# source_eagle.net
KiCad netlist of a schematic drawn in EAGLE
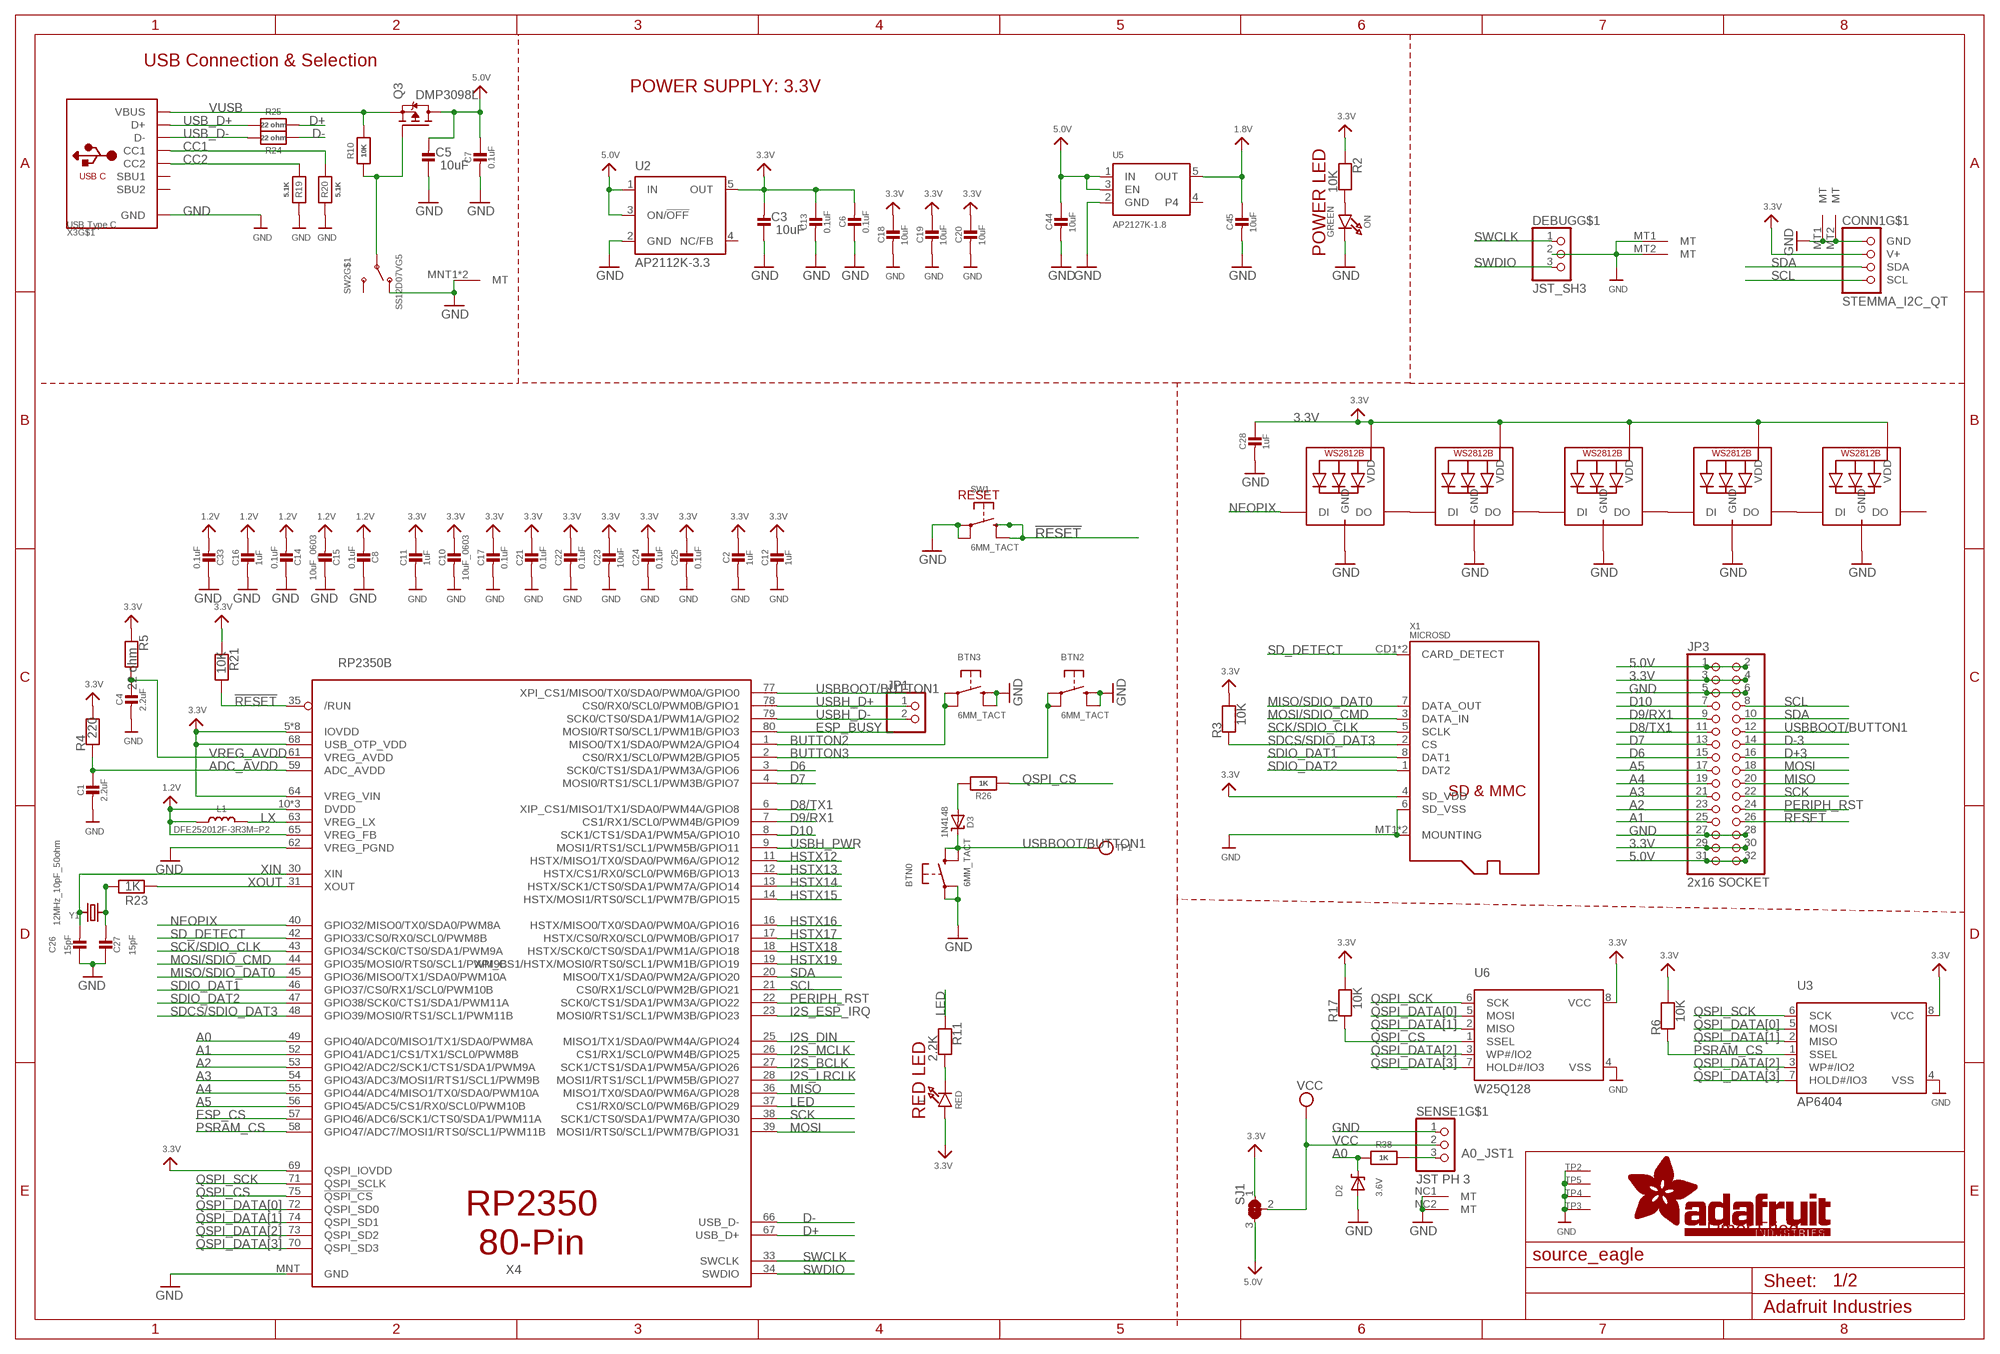
[diagram p0: schematic, sheet 1]
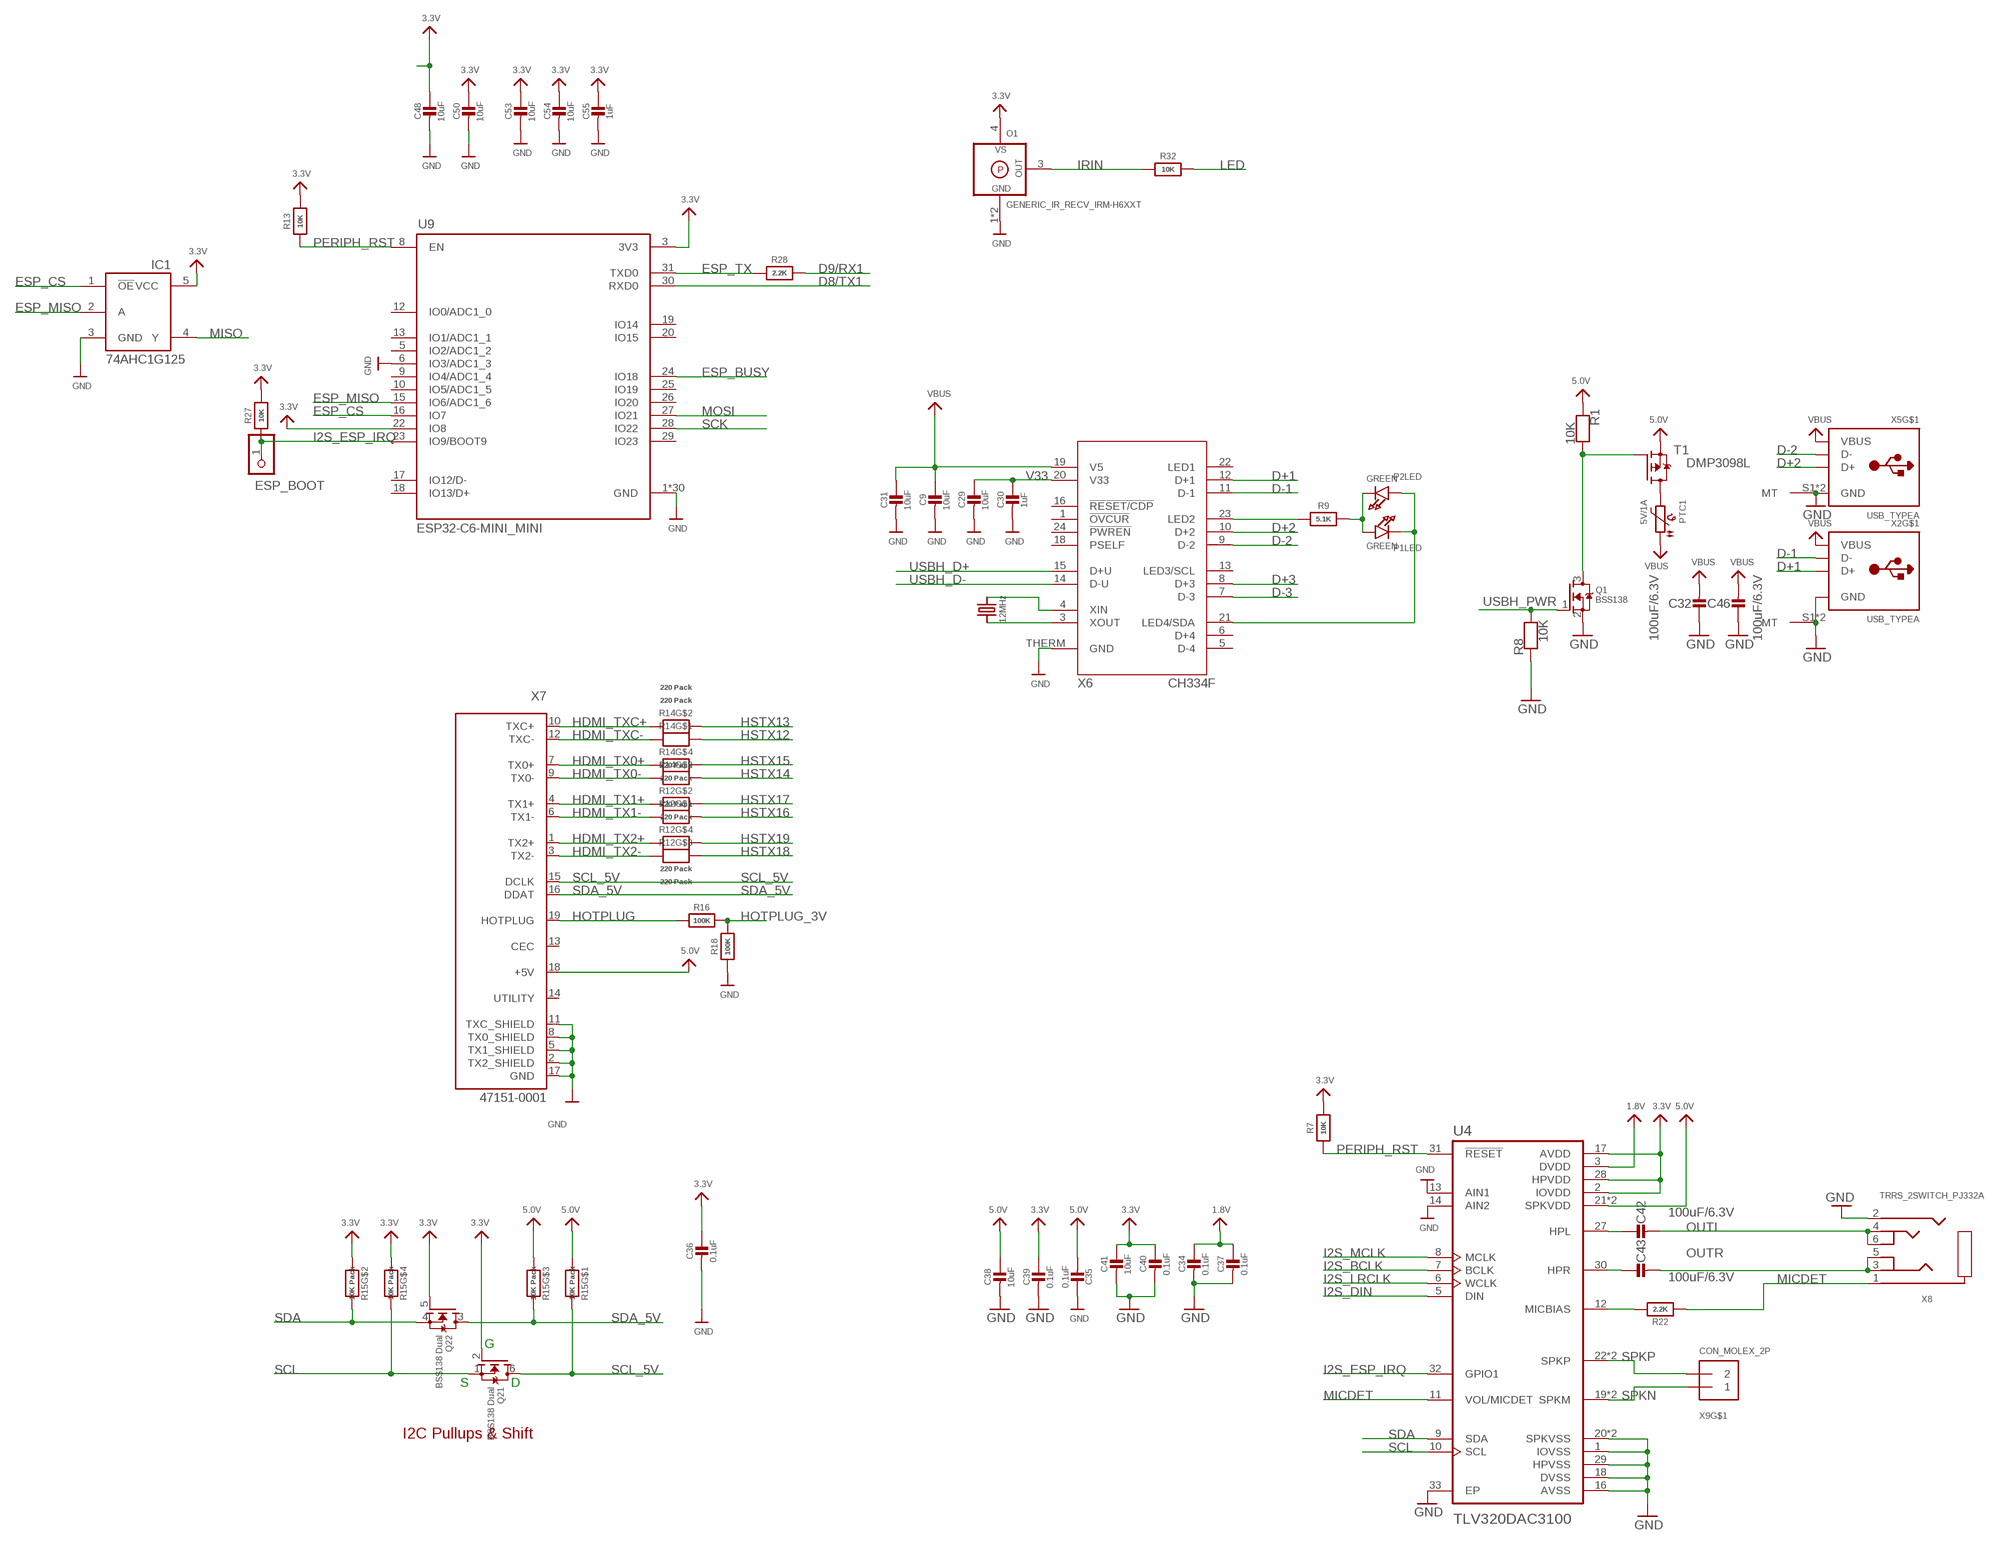
[diagram p1: schematic, sheet 2]

(export (version "E")
  (design (tool "Eeschema 10.0.6"))
  (components
    (comp (ref "BTN0")
      (value "6MM_TACT")
      (footprint "eagle-import:EVQ-Q2")
      (libsource (lib "eagle-import") (part "SWITCH_TACT_SMT"))
    )
    (comp (ref "BTN2")
      (value "6MM_TACT")
      (footprint "eagle-import:EVQ-Q2")
      (libsource (lib "eagle-import") (part "SWITCH_TACT_SMT"))
    )
    (comp (ref "BTN3")
      (value "6MM_TACT")
      (footprint "eagle-import:EVQ-Q2")
      (libsource (lib "eagle-import") (part "SWITCH_TACT_SMT"))
    )
    (comp (ref "C1")
      (value "2.2uF")
      (footprint "eagle-import:0603-NO")
      (libsource (lib "eagle-import") (part "CAP_CERAMIC0603_NO"))
    )
    (comp (ref "C2")
      (value "1uF")
      (footprint "eagle-import:0603-NO")
      (libsource (lib "eagle-import") (part "CAP_CERAMIC0603_NO"))
    )
    (comp (ref "C3")
      (value "10uF")
      (footprint "eagle-import:0805-NO")
      (libsource (lib "eagle-import") (part "CAP_CERAMIC0805-NOOUTLINE"))
    )
    (comp (ref "C4")
      (value "2.2uF")
      (footprint "eagle-import:0603-NO")
      (libsource (lib "eagle-import") (part "CAP_CERAMIC0603_NO"))
    )
    (comp (ref "C5")
      (value "10uF")
      (footprint "eagle-import:0805-NO")
      (libsource (lib "eagle-import") (part "CAP_CERAMIC0805-NOOUTLINE"))
    )
    (comp (ref "C6")
      (value "0.1uF")
      (footprint "eagle-import:0603-NO")
      (libsource (lib "eagle-import") (part "CAP_CERAMIC0603_NO"))
    )
    (comp (ref "C7")
      (value "0.1uF")
      (footprint "eagle-import:0603-NO")
      (libsource (lib "eagle-import") (part "CAP_CERAMIC0603_NO"))
    )
    (comp (ref "C8")
      (value "0.1uF")
      (footprint "eagle-import:0603-NO")
      (libsource (lib "eagle-import") (part "CAP_CERAMIC0603_NO"))
    )
    (comp (ref "C10")
      (value "10uF_0603")
      (footprint "eagle-import:0603-NO_WIDE")
      (libsource (lib "eagle-import") (part "CAP_CERAMIC_0603WIDE"))
    )
    (comp (ref "C11")
      (value "1uF")
      (footprint "eagle-import:0603-NO")
      (libsource (lib "eagle-import") (part "CAP_CERAMIC0603_NO"))
    )
    (comp (ref "C12")
      (value "1uF")
      (footprint "eagle-import:0603-NO")
      (libsource (lib "eagle-import") (part "CAP_CERAMIC0603_NO"))
    )
    (comp (ref "C13")
      (value "0.1uF")
      (footprint "eagle-import:0603-NO")
      (libsource (lib "eagle-import") (part "CAP_CERAMIC0603_NO"))
    )
    (comp (ref "C14")
      (value "0.1uF")
      (footprint "eagle-import:0603-NO")
      (libsource (lib "eagle-import") (part "CAP_CERAMIC0603_NO"))
    )
    (comp (ref "C15")
      (value "10uF_0603")
      (footprint "eagle-import:0603-NO_WIDE")
      (libsource (lib "eagle-import") (part "CAP_CERAMIC_0603WIDE"))
    )
    (comp (ref "C16")
      (value "1uF")
      (footprint "eagle-import:0603-NO")
      (libsource (lib "eagle-import") (part "CAP_CERAMIC0603_NO"))
    )
    (comp (ref "C17")
      (value "0.1uF")
      (footprint "eagle-import:0603-NO")
      (libsource (lib "eagle-import") (part "CAP_CERAMIC0603_NO"))
    )
    (comp (ref "C18")
      (value "10uF")
      (footprint "eagle-import:0805-NO")
      (libsource (lib "eagle-import") (part "CAP_CERAMIC0805-NOOUTLINE"))
    )
    (comp (ref "C19")
      (value "10uF")
      (footprint "eagle-import:0805-NO")
      (libsource (lib "eagle-import") (part "CAP_CERAMIC0805-NOOUTLINE"))
    )
    (comp (ref "C20")
      (value "10uF")
      (footprint "eagle-import:0805-NO")
      (libsource (lib "eagle-import") (part "CAP_CERAMIC0805-NOOUTLINE"))
    )
    (comp (ref "C21")
      (value "0.1uF")
      (footprint "eagle-import:0603-NO")
      (libsource (lib "eagle-import") (part "CAP_CERAMIC0603_NO"))
    )
    (comp (ref "C22")
      (value "0.1uF")
      (footprint "eagle-import:0603-NO")
      (libsource (lib "eagle-import") (part "CAP_CERAMIC0603_NO"))
    )
    (comp (ref "C23")
      (value "10uF")
      (footprint "eagle-import:0805-NO")
      (libsource (lib "eagle-import") (part "CAP_CERAMIC0805-NOOUTLINE"))
    )
    (comp (ref "C24")
      (value "0.1uF")
      (footprint "eagle-import:0603-NO")
      (libsource (lib "eagle-import") (part "CAP_CERAMIC0603_NO"))
    )
    (comp (ref "C25")
      (value "0.1uF")
      (footprint "eagle-import:0603-NO")
      (libsource (lib "eagle-import") (part "CAP_CERAMIC0603_NO"))
    )
    (comp (ref "C26")
      (value "15pF")
      (footprint "eagle-import:0603-NO")
      (libsource (lib "eagle-import") (part "CAP_CERAMIC0603_NO"))
    )
    (comp (ref "C27")
      (value "15pF")
      (footprint "eagle-import:0603-NO")
      (libsource (lib "eagle-import") (part "CAP_CERAMIC0603_NO"))
    )
    (comp (ref "C28")
      (value "1uF")
      (footprint "eagle-import:0603-NO")
      (libsource (lib "eagle-import") (part "CAP_CERAMIC0603_NO"))
    )
    (comp (ref "C33")
      (value "0.1uF")
      (footprint "eagle-import:0603-NO")
      (libsource (lib "eagle-import") (part "CAP_CERAMIC0603_NO"))
    )
    (comp (ref "C44")
      (value "10uF")
      (footprint "eagle-import:0805-NO")
      (libsource (lib "eagle-import") (part "CAP_CERAMIC0805-NOOUTLINE"))
    )
    (comp (ref "C45")
      (value "10uF")
      (footprint "eagle-import:0805-NO")
      (libsource (lib "eagle-import") (part "CAP_CERAMIC0805-NOOUTLINE"))
    )
    (comp (ref "CONN1")
      (value "STEMMA_I2C_QT")
      (footprint "eagle-import:JST_SH4")
      (libsource (lib "eagle-import") (part "STEMMA_I2C_QT"))
    )
    (comp (ref "D2")
      (value "3.6V")
      (footprint "eagle-import:SOD-323")
      (libsource (lib "eagle-import") (part "DIODE-ZENERSOD323"))
    )
    (comp (ref "D3")
      (value "1N4148")
      (footprint "eagle-import:SOD-323")
      (libsource (lib "eagle-import") (part "DIODE-SCHOTTKYSOD-323"))
    )
    (comp (ref "DEBUG")
      (value "JST_SH3")
      (footprint "eagle-import:JST_SH3_RA")
      (libsource (lib "eagle-import") (part "CON_JST_SH_3PINVERT"))
    )
    (comp (ref "JP1")
      (value "HEADER-1X2ROUND")
      (footprint "eagle-import:1X02_ROUND")
      (libsource (lib "eagle-import") (part "HEADER-1X2ROUND"))
    )
    (comp (ref "JP3")
      (value "2x16 SOCKET")
      (footprint "eagle-import:2X16")
      (libsource (lib "eagle-import") (part "PINHD-2X16"))
    )
    (comp (ref "L")
      (value "RED")
      (footprint "eagle-import:CHIPLED_0603_NOOUTLINE")
      (libsource (lib "eagle-import") (part "LED0603_NOOUTLINE"))
    )
    (comp (ref "L1")
      (value "DFE252012F-3R3M=P2")
      (footprint "eagle-import:INDUCTOR_1007")
      (libsource (lib "eagle-import") (part "INDUCTOR"))
    )
    (comp (ref "LED1")
      (value "WS2812B_3535FULL")
      (footprint "eagle-import:LED3535_FULLPADS")
      (libsource (lib "eagle-import") (part "WS2812B_3535FULL"))
    )
    (comp (ref "LED2")
      (value "WS2812B_3535FULL")
      (footprint "eagle-import:LED3535_FULLPADS")
      (libsource (lib "eagle-import") (part "WS2812B_3535FULL"))
    )
    (comp (ref "LED3")
      (value "WS2812B_3535FULL")
      (footprint "eagle-import:LED3535_FULLPADS")
      (libsource (lib "eagle-import") (part "WS2812B_3535FULL"))
    )
    (comp (ref "LED4")
      (value "WS2812B_3535FULL")
      (footprint "eagle-import:LED3535_FULLPADS")
      (libsource (lib "eagle-import") (part "WS2812B_3535FULL"))
    )
    (comp (ref "LED5")
      (value "WS2812B_3535FULL")
      (footprint "eagle-import:LED3535_FULLPADS")
      (libsource (lib "eagle-import") (part "WS2812B_3535FULL"))
    )
    (comp (ref "ON")
      (value "GREEN")
      (footprint "eagle-import:CHIPLED_0603_NOOUTLINE")
      (libsource (lib "eagle-import") (part "LED0603_NOOUTLINE"))
    )
    (comp (ref "Q3")
      (value "DMP3098L")
      (footprint "eagle-import:SOT23-WIDE")
      (libsource (lib "eagle-import") (part "MOSFET-PWIDE"))
    )
    (comp (ref "R2")
      (value "10K")
      (footprint "eagle-import:0603-NO")
      (libsource (lib "eagle-import") (part "RESISTOR_0603_NOOUT"))
    )
    (comp (ref "R3")
      (value "10K")
      (footprint "eagle-import:0603-NO")
      (libsource (lib "eagle-import") (part "RESISTOR_0603_NOOUT"))
    )
    (comp (ref "R4")
      (value "220")
      (footprint "eagle-import:0603-NO")
      (libsource (lib "eagle-import") (part "RESISTOR_0603_NOOUT"))
    )
    (comp (ref "R5")
      (value "22 ohm")
      (footprint "eagle-import:0603-NO")
      (libsource (lib "eagle-import") (part "RESISTOR_0603_NOOUT"))
    )
    (comp (ref "R6")
      (value "10K")
      (footprint "eagle-import:0603-NO")
      (libsource (lib "eagle-import") (part "RESISTOR_0603_NOOUT"))
    )
    (comp (ref "R10")
      (value "10K")
      (footprint "eagle-import:0603-NO")
      (libsource (lib "eagle-import") (part "RESISTOR_0603_NOOUT"))
    )
    (comp (ref "R11")
      (value "2.2K")
      (footprint "eagle-import:0603-NO")
      (libsource (lib "eagle-import") (part "RESISTOR_0603_NOOUT"))
    )
    (comp (ref "R17")
      (value "10K")
      (footprint "eagle-import:0603-NO")
      (libsource (lib "eagle-import") (part "RESISTOR_0603_NOOUT"))
    )
    (comp (ref "R19")
      (value "5.1K")
      (footprint "eagle-import:0603-NO")
      (libsource (lib "eagle-import") (part "RESISTOR_0603_NOOUT"))
    )
    (comp (ref "R20")
      (value "5.1K")
      (footprint "eagle-import:0603-NO")
      (libsource (lib "eagle-import") (part "RESISTOR_0603_NOOUT"))
    )
    (comp (ref "R21")
      (value "10K")
      (footprint "eagle-import:0603-NO")
      (libsource (lib "eagle-import") (part "RESISTOR_0603_NOOUT"))
    )
    (comp (ref "R23")
      (value "1K")
      (footprint "eagle-import:0603-NO")
      (libsource (lib "eagle-import") (part "RESISTOR_0603_NOOUT"))
    )
    (comp (ref "R24")
      (value "22 ohm")
      (footprint "eagle-import:0603-NO")
      (libsource (lib "eagle-import") (part "RESISTOR_0603_NOOUT"))
    )
    (comp (ref "R25")
      (value "22 ohm")
      (footprint "eagle-import:0603-NO")
      (libsource (lib "eagle-import") (part "RESISTOR_0603_NOOUT"))
    )
    (comp (ref "R26")
      (value "1K")
      (footprint "eagle-import:0603-NO")
      (libsource (lib "eagle-import") (part "RESISTOR_0603_NOOUT"))
    )
    (comp (ref "R38")
      (value "1K")
      (footprint "eagle-import:0603-NO")
      (libsource (lib "eagle-import") (part "RESISTOR_0603_NOOUT"))
    )
    (comp (ref "SENSE1")
      (value "JST PH 3")
      (footprint "eagle-import:JSTPH3")
      (libsource (lib "eagle-import") (part "CON_JST_PH_3PIN"))
    )
    (comp (ref "SJ1")
      (value "SOLDERJUMPER_2WAY")
      (footprint "eagle-import:SOLDERJUMPER_2WAY_OPEN_NOPASTE")
      (libsource (lib "eagle-import") (part "SOLDERJUMPER_2WAY"))
    )
    (comp (ref "SW1")
      (value "6MM_TACT")
      (footprint "eagle-import:EVQ-Q2")
      (libsource (lib "eagle-import") (part "SWITCH_TACT_SMT"))
    )
    (comp (ref "SW2")
      (value "SS12D07VG5")
      (footprint "eagle-import:SPDT_SS12D07VG5")
      (libsource (lib "eagle-import") (part "SWITCH_SPDTSS12D07VG5"))
    )
    (comp (ref "TP1")
      (value "TESTPOINTROUND1.5MMNO")
      (footprint "eagle-import:TESTPOINT_ROUND_1.5MM_NO")
      (libsource (lib "eagle-import") (part "TESTPOINTROUND1.5MMNO"))
    )
    (comp (ref "TP2")
      (value "DNP")
      (footprint "eagle-import:SMT_NUT_3MM")
      (libsource (lib "eagle-import") (part "SEWTAP_SMTNUTM3"))
    )
    (comp (ref "TP3")
      (value "SEWTAP_SMTNUTM3")
      (footprint "eagle-import:SMT_NUT_3MM")
      (libsource (lib "eagle-import") (part "SEWTAP_SMTNUTM3"))
    )
    (comp (ref "TP4")
      (value "SEWTAP_SMTNUTM3")
      (footprint "eagle-import:SMT_NUT_3MM")
      (libsource (lib "eagle-import") (part "SEWTAP_SMTNUTM3"))
    )
    (comp (ref "TP5")
      (value "SEWTAP_SMTNUTM3")
      (footprint "eagle-import:SMT_NUT_3MM")
      (libsource (lib "eagle-import") (part "SEWTAP_SMTNUTM3"))
    )
    (comp (ref "U2")
      (value "AP2112K-3.3")
      (footprint "eagle-import:SOT23-DBV")
      (libsource (lib "eagle-import") (part "LP2985-XXDBVR33"))
    )
    (comp (ref "U3")
      (value "AP6404")
      (footprint "eagle-import:SOIC8_208MIL")
      (libsource (lib "eagle-import") (part "SPIFLASH_8PIN208MIL"))
    )
    (comp (ref "U5")
      (value "AP2127K-1.8")
      (footprint "eagle-import:SOT23-5")
      (libsource (lib "eagle-import") (part "VREG_SOT23-5"))
    )
    (comp (ref "U6")
      (value "W25Q128")
      (footprint "eagle-import:SOIC8_208MIL")
      (libsource (lib "eagle-import") (part "SPIFLASH_8PIN208MIL"))
    )
    (comp (ref "X1")
      (value "MICROSD")
      (footprint "eagle-import:MICROSD")
      (libsource (lib "eagle-import") (part "MICROSD"))
    )
    (comp (ref "X3")
      (value "USB Type C")
      (footprint "eagle-import:USB_C_CUSB31-CFM2AX-01-X")
      (libsource (lib "eagle-import") (part "USB_C"))
    )
    (comp (ref "X4")
      (value "RP2350B")
      (footprint "eagle-import:QFN80")
      (libsource (lib "eagle-import") (part "RP2350B"))
    )
    (comp (ref "Y1")
      (value "12MHz_10pF_50ohm")
      (footprint "eagle-import:CRYSTAL_2.5X2")
      (libsource (lib "eagle-import") (part "CRYSTAL2.5X2.0"))
    )
    (comp (ref "C9")
      (value "10uF")
      (footprint "eagle-import:0805-NO")
      (libsource (lib "eagle-import") (part "CAP_CERAMIC0805-NOOUTLINE"))
    )
    (comp (ref "C29")
      (value "10uF")
      (footprint "eagle-import:0805-NO")
      (libsource (lib "eagle-import") (part "CAP_CERAMIC0805-NOOUTLINE"))
    )
    (comp (ref "C30")
      (value "1uF")
      (footprint "eagle-import:0603-NO")
      (libsource (lib "eagle-import") (part "CAP_CERAMIC0603_NO"))
    )
    (comp (ref "C31")
      (value "10uF")
      (footprint "eagle-import:0805-NO")
      (libsource (lib "eagle-import") (part "CAP_CERAMIC0805-NOOUTLINE"))
    )
    (comp (ref "C32")
      (value "100uF/6.3V")
      (footprint "eagle-import:_1206")
      (libsource (lib "eagle-import") (part "CAP_CERAMIC_1206"))
    )
    (comp (ref "C34")
      (value "0.1uF")
      (footprint "eagle-import:0603-NO")
      (libsource (lib "eagle-import") (part "CAP_CERAMIC0603_NO"))
    )
    (comp (ref "C35")
      (value "0.1uF")
      (footprint "eagle-import:0603-NO")
      (libsource (lib "eagle-import") (part "CAP_CERAMIC0603_NO"))
    )
    (comp (ref "C36")
      (value "0.1uF")
      (footprint "eagle-import:0603-NO")
      (libsource (lib "eagle-import") (part "CAP_CERAMIC0603_NO"))
    )
    (comp (ref "C37")
      (value "0.1uF")
      (footprint "eagle-import:0603-NO")
      (libsource (lib "eagle-import") (part "CAP_CERAMIC0603_NO"))
    )
    (comp (ref "C38")
      (value "10uF")
      (footprint "eagle-import:0805-NO")
      (libsource (lib "eagle-import") (part "CAP_CERAMIC0805-NOOUTLINE"))
    )
    (comp (ref "C39")
      (value "0.1uF")
      (footprint "eagle-import:0603-NO")
      (libsource (lib "eagle-import") (part "CAP_CERAMIC0603_NO"))
    )
    (comp (ref "C40")
      (value "0.1uF")
      (footprint "eagle-import:0603-NO")
      (libsource (lib "eagle-import") (part "CAP_CERAMIC0603_NO"))
    )
    (comp (ref "C41")
      (value "10uF")
      (footprint "eagle-import:0805-NO")
      (libsource (lib "eagle-import") (part "CAP_CERAMIC0805-NOOUTLINE"))
    )
    (comp (ref "C42")
      (value "100uF/6.3V")
      (footprint "eagle-import:_1206")
      (libsource (lib "eagle-import") (part "CAP_CERAMIC_1206"))
    )
    (comp (ref "C43")
      (value "100uF/6.3V")
      (footprint "eagle-import:_1206")
      (libsource (lib "eagle-import") (part "CAP_CERAMIC_1206"))
    )
    (comp (ref "C46")
      (value "100uF/6.3V")
      (footprint "eagle-import:_1206")
      (libsource (lib "eagle-import") (part "CAP_CERAMIC_1206"))
    )
    (comp (ref "C48")
      (value "10uF")
      (footprint "eagle-import:0805-NO")
      (fields (field (name "REV") "C"))
      (libsource (lib "eagle-import") (part "CAP_CERAMIC0805-NOOUTLINE"))
    )
    (comp (ref "C50")
      (value "10uF")
      (footprint "eagle-import:0805-NO")
      (libsource (lib "eagle-import") (part "CAP_CERAMIC0805-NOOUTLINE"))
    )
    (comp (ref "C53")
      (value "10uF")
      (footprint "eagle-import:0805-NO")
      (libsource (lib "eagle-import") (part "CAP_CERAMIC0805-NOOUTLINE"))
    )
    (comp (ref "C54")
      (value "10uF")
      (footprint "eagle-import:0805-NO")
      (libsource (lib "eagle-import") (part "CAP_CERAMIC0805-NOOUTLINE"))
    )
    (comp (ref "C55")
      (value "1uF")
      (footprint "eagle-import:0603-NO")
      (libsource (lib "eagle-import") (part "CAP_CERAMIC0603_NO"))
    )
    (comp (ref "ESP_BOOT")
      (value "HEADER-1X1ROUND")
      (footprint "eagle-import:1X01_ROUND")
      (libsource (lib "eagle-import") (part "HEADER-1X1ROUND"))
    )
    (comp (ref "IC1")
      (value "74AHC1G125")
      (footprint "eagle-import:SOT23-5L")
      (libsource (lib "eagle-import") (part "74AHC1G125"))
    )
    (comp (ref "O1")
      (value "GENERIC_IR_RECV_IRM-H6XXT")
      (footprint "eagle-import:IRM-H6XXT")
      (libsource (lib "eagle-import") (part "GENERIC_IR_RECV_IRM-H6XXT"))
    )
    (comp (ref "P1LED")
      (value "GREEN")
      (footprint "eagle-import:CHIPLED_0603_NOOUTLINE")
      (libsource (lib "eagle-import") (part "LED0603_NOOUTLINE"))
    )
    (comp (ref "P2LED")
      (value "GREEN")
      (footprint "eagle-import:CHIPLED_0603_NOOUTLINE")
      (libsource (lib "eagle-import") (part "LED0603_NOOUTLINE"))
    )
    (comp (ref "PTC1")
      (value "5V/1A")
      (footprint "eagle-import:0805-NO")
      (libsource (lib "eagle-import") (part "PTC_0805"))
    )
    (comp (ref "Q1")
      (value "BSS138")
      (footprint "eagle-import:SOT23-WIDE")
      (libsource (lib "eagle-import") (part "MOSFET-NWIDE"))
    )
    (comp (ref "Q2")
      (value "BSS138 Dual")
      (footprint "eagle-import:SOT363")
      (libsource (lib "eagle-import") (part "MOSFET-N_DUAL"))
    )
    (comp (ref "R1")
      (value "10K")
      (footprint "eagle-import:0603-NO")
      (libsource (lib "eagle-import") (part "RESISTOR_0603_NOOUT"))
    )
    (comp (ref "R7")
      (value "10K")
      (footprint "eagle-import:0603-NO")
      (libsource (lib "eagle-import") (part "RESISTOR_0603_NOOUT"))
    )
    (comp (ref "R8")
      (value "10K")
      (footprint "eagle-import:0603-NO")
      (libsource (lib "eagle-import") (part "RESISTOR_0603_NOOUT"))
    )
    (comp (ref "R9")
      (value "5.1K")
      (footprint "eagle-import:0603-NO")
      (libsource (lib "eagle-import") (part "RESISTOR_0603_NOOUT"))
    )
    (comp (ref "R12")
      (value "220 Pack")
      (footprint "eagle-import:RESPACK_4X0603")
      (libsource (lib "eagle-import") (part "RESISTOR_4PACK"))
    )
    (comp (ref "R13")
      (value "10K")
      (footprint "eagle-import:0603-NO")
      (libsource (lib "eagle-import") (part "RESISTOR_0603_NOOUT"))
    )
    (comp (ref "R14")
      (value "220 Pack")
      (footprint "eagle-import:RESPACK_4X0603")
      (libsource (lib "eagle-import") (part "RESISTOR_4PACK"))
    )
    (comp (ref "R15")
      (value "10K Pack")
      (footprint "eagle-import:RESPACK_4X0603")
      (libsource (lib "eagle-import") (part "RESISTOR_4PACK"))
    )
    (comp (ref "R16")
      (value "100K")
      (footprint "eagle-import:0603-NO")
      (libsource (lib "eagle-import") (part "RESISTOR_0603_NOOUT"))
    )
    (comp (ref "R18")
      (value "100K")
      (footprint "eagle-import:0603-NO")
      (libsource (lib "eagle-import") (part "RESISTOR_0603_NOOUT"))
    )
    (comp (ref "R22")
      (value "2.2K")
      (footprint "eagle-import:0603-NO")
      (libsource (lib "eagle-import") (part "RESISTOR_0603_NOOUT"))
    )
    (comp (ref "R27")
      (value "10K")
      (footprint "eagle-import:0603-NO")
      (libsource (lib "eagle-import") (part "RESISTOR_0603_NOOUT"))
    )
    (comp (ref "R28")
      (value "2.2K")
      (footprint "eagle-import:0603-NO")
      (libsource (lib "eagle-import") (part "RESISTOR_0603_NOOUT"))
    )
    (comp (ref "R32")
      (value "10K")
      (footprint "eagle-import:0603-NO")
      (libsource (lib "eagle-import") (part "RESISTOR_0603_NOOUT"))
    )
    (comp (ref "T1")
      (value "DMP3098L")
      (footprint "eagle-import:SOT23-WIDE")
      (libsource (lib "eagle-import") (part "MOSFET-PWIDE"))
    )
    (comp (ref "U4")
      (value "TLV320DAC3100")
      (footprint "eagle-import:TLV320DAC3100")
      (libsource (lib "eagle-import") (part "TLV320DAC3100"))
    )
    (comp (ref "U9")
      (value "ESP32-C6-MINI_MINI")
      (footprint "eagle-import:ESP32-PICO-MINI")
      (libsource (lib "eagle-import") (part "ESP32-C6-MINI_MINI"))
    )
    (comp (ref "X2")
      (value "USB_TYPEA")
      (footprint "eagle-import:USB_TYPE_A_THM_SHORT")
      (libsource (lib "eagle-import") (part "USB_TYPEA_THMSHORT"))
    )
    (comp (ref "X5")
      (value "USB_TYPEA")
      (footprint "eagle-import:USB_TYPE_A_THM_SHORT")
      (libsource (lib "eagle-import") (part "USB_TYPEA_THMSHORT"))
    )
    (comp (ref "X6")
      (value "CH334F")
      (footprint "eagle-import:QFN24_4MM")
      (libsource (lib "eagle-import") (part "CH334F"))
    )
    (comp (ref "X7")
      (value "47151-0001")
      (footprint "eagle-import:HDMI_MOLEX_47151-0001")
      (libsource (lib "eagle-import") (part "HDMI_MOLEX_47151"))
    )
    (comp (ref "X8")
      (value "TRRS_2SWITCH_PJ332A")
      (footprint "eagle-import:PJ-332A")
      (libsource (lib "eagle-import") (part "TRRS_2SWITCH_PJ332A"))
    )
    (comp (ref "X9")
      (value "CON_MOLEX_2P")
      (footprint "eagle-import:53398-0271")
      (libsource (lib "eagle-import") (part "CON_MOLEX_2P"))
    )
    (comp (ref "Y2")
      (value "12MHz")
      (footprint "eagle-import:CRYSTAL_2.5X2")
      (libsource (lib "eagle-import") (part "CRYSTAL2.5X2.0"))
    )
  )
  (nets
    (net (code "1") (name "1.2V") (class "Default")
      (node (ref "C14") (pin "2") (pinfunction "2_2") (pintype "passive"))
      (node (ref "C15") (pin "2") (pinfunction "2_2") (pintype "passive"))
      (node (ref "C16") (pin "1") (pinfunction "1_1") (pintype "passive"))
      (node (ref "C33") (pin "2") (pinfunction "2_2") (pintype "passive"))
      (node (ref "C8") (pin "2") (pinfunction "2_2") (pintype "passive"))
      (node (ref "L1") (pin "P$1") (pinfunction "1_P$1") (pintype "passive"))
      (node (ref "X4") (pin "10") (pinfunction "DVDD_10") (pintype "power_in"))
      (node (ref "X4") (pin "32") (pinfunction "DVDD_32") (pintype "power_in"))
      (node (ref "X4") (pin "51") (pinfunction "DVDD_51") (pintype "power_in"))
      (node (ref "X4") (pin "65") (pinfunction "VREG_FB_65") (pintype "input"))
    )
    (net (code "2") (name "1.8V") (class "Default")
      (node (ref "C34") (pin "1") (pinfunction "1_1") (pintype "passive"))
      (node (ref "C37") (pin "1") (pinfunction "1_1") (pintype "passive"))
      (node (ref "C45") (pin "1") (pinfunction "1_1") (pintype "passive"))
      (node (ref "U4") (pin "3") (pinfunction "DVDD_3") (pintype "power_in"))
      (node (ref "U5") (pin "5") (pinfunction "OUT_5") (pintype "power_in"))
    )
    (net (code "3") (name "3.3V") (class "Default")
      (node (ref "C10") (pin "1") (pinfunction "1_1") (pintype "passive"))
      (node (ref "C11") (pin "1") (pinfunction "1_1") (pintype "passive"))
      (node (ref "C12") (pin "1") (pinfunction "1_1") (pintype "passive"))
      (node (ref "C13") (pin "1") (pinfunction "1_1") (pintype "passive"))
      (node (ref "C17") (pin "1") (pinfunction "1_1") (pintype "passive"))
      (node (ref "C18") (pin "1") (pinfunction "1_1") (pintype "passive"))
      (node (ref "C19") (pin "1") (pinfunction "1_1") (pintype "passive"))
      (node (ref "C2") (pin "1") (pinfunction "1_1") (pintype "passive"))
      (node (ref "C20") (pin "1") (pinfunction "1_1") (pintype "passive"))
      (node (ref "C21") (pin "1") (pinfunction "1_1") (pintype "passive"))
      (node (ref "C22") (pin "1") (pinfunction "1_1") (pintype "passive"))
      (node (ref "C23") (pin "1") (pinfunction "1_1") (pintype "passive"))
      (node (ref "C24") (pin "1") (pinfunction "1_1") (pintype "passive"))
      (node (ref "C25") (pin "1") (pinfunction "1_1") (pintype "passive"))
      (node (ref "C28") (pin "1") (pinfunction "1_1") (pintype "passive"))
      (node (ref "C3") (pin "2") (pinfunction "2_2") (pintype "passive"))
      (node (ref "C36") (pin "1") (pinfunction "1_1") (pintype "passive"))
      (node (ref "C39") (pin "1") (pinfunction "1_1") (pintype "passive"))
      (node (ref "C40") (pin "1") (pinfunction "1_1") (pintype "passive"))
      (node (ref "C41") (pin "1") (pinfunction "1_1") (pintype "passive"))
      (node (ref "C48") (pin "1") (pinfunction "1_1") (pintype "passive"))
      (node (ref "C50") (pin "1") (pinfunction "1_1") (pintype "passive"))
      (node (ref "C53") (pin "1") (pinfunction "1_1") (pintype "passive"))
      (node (ref "C54") (pin "1") (pinfunction "1_1") (pintype "passive"))
      (node (ref "C55") (pin "1") (pinfunction "1_1") (pintype "passive"))
      (node (ref "C6") (pin "2") (pinfunction "2_2") (pintype "passive"))
      (node (ref "CONN1") (pin "2") (pinfunction "V+_2") (pintype "passive"))
      (node (ref "IC1") (pin "5") (pinfunction "VCC_5") (pintype "power_in"))
      (node (ref "JP3") (pin "29") (pinfunction "29_29") (pintype "passive"))
      (node (ref "JP3") (pin "3") (pinfunction "3_3") (pintype "passive"))
      (node (ref "JP3") (pin "30") (pinfunction "30_30") (pintype "passive"))
      (node (ref "JP3") (pin "4") (pinfunction "4_4") (pintype "passive"))
      (node (ref "L") (pin "A") (pinfunction "A_A") (pintype "passive"))
      (node (ref "LED1") (pin "2") (pinfunction "VDD_2") (pintype "power_in"))
      (node (ref "LED2") (pin "2") (pinfunction "VDD_2") (pintype "power_in"))
      (node (ref "LED3") (pin "2") (pinfunction "VDD_2") (pintype "power_in"))
      (node (ref "LED4") (pin "2") (pinfunction "VDD_2") (pintype "power_in"))
      (node (ref "LED5") (pin "2") (pinfunction "VDD_2") (pintype "power_in"))
      (node (ref "O1") (pin "4") (pinfunction "VS_4") (pintype "power_in"))
      (node (ref "Q2") (pin "2") (pinfunction "G_2") (pintype "bidirectional"))
      (node (ref "Q2") (pin "5") (pinfunction "G_5") (pintype "bidirectional"))
      (node (ref "R13") (pin "2") (pinfunction "2_2") (pintype "passive"))
      (node (ref "R15") (pin "5") (pinfunction "2_5") (pintype "passive"))
      (node (ref "R15") (pin "7") (pinfunction "2_7") (pintype "passive"))
      (node (ref "R17") (pin "2") (pinfunction "2_2") (pintype "passive"))
      (node (ref "R2") (pin "1") (pinfunction "1_1") (pintype "passive"))
      (node (ref "R21") (pin "1") (pinfunction "1_1") (pintype "passive"))
      (node (ref "R27") (pin "2") (pinfunction "2_2") (pintype "passive"))
      (node (ref "R3") (pin "2") (pinfunction "2_2") (pintype "passive"))
      (node (ref "R4") (pin "2") (pinfunction "2_2") (pintype "passive"))
      (node (ref "R5") (pin "1") (pinfunction "1_1") (pintype "passive"))
      (node (ref "R6") (pin "2") (pinfunction "2_2") (pintype "passive"))
      (node (ref "R7") (pin "2") (pinfunction "2_2") (pintype "passive"))
      (node (ref "SJ1") (pin "1") (pinfunction "1_1") (pintype "passive"))
      (node (ref "U2") (pin "5") (pinfunction "OUT_5") (pintype "passive"))
      (node (ref "U3") (pin "8") (pinfunction "VCC_8") (pintype "bidirectional"))
      (node (ref "U4") (pin "17") (pinfunction "AVDD_17") (pintype "power_in"))
      (node (ref "U4") (pin "2") (pinfunction "IOVDD_2") (pintype "power_in"))
      (node (ref "U4") (pin "28") (pinfunction "HPVDD_28") (pintype "power_in"))
      (node (ref "U6") (pin "8") (pinfunction "VCC_8") (pintype "bidirectional"))
      (node (ref "U9") (pin "22") (pinfunction "IO8_22") (pintype "bidirectional"))
      (node (ref "U9") (pin "3") (pinfunction "3V3_3") (pintype "power_in"))
      (node (ref "X1") (pin "4") (pinfunction "SD_VDD_4") (pintype "power_in"))
      (node (ref "X4") (pin "15") (pinfunction "IOVDD_15") (pintype "power_in"))
      (node (ref "X4") (pin "24") (pinfunction "IOVDD_24") (pintype "power_in"))
      (node (ref "X4") (pin "29") (pinfunction "IOVDD_29") (pintype "power_in"))
      (node (ref "X4") (pin "41") (pinfunction "IOVDD_41") (pintype "power_in"))
      (node (ref "X4") (pin "5") (pinfunction "IOVDD_5") (pintype "power_in"))
      (node (ref "X4") (pin "50") (pinfunction "IOVDD_50") (pintype "power_in"))
      (node (ref "X4") (pin "60") (pinfunction "IOVDD_60") (pintype "power_in"))
      (node (ref "X4") (pin "64") (pinfunction "VREG_VIN_64") (pintype "input"))
      (node (ref "X4") (pin "68") (pinfunction "USB_OTP_VDD_68") (pintype "power_in"))
      (node (ref "X4") (pin "69") (pinfunction "QSPI_IOVDD_69") (pintype "power_in"))
      (node (ref "X4") (pin "76") (pinfunction "IOVDD_76") (pintype "power_in"))
    )
    (net (code "4") (name "5.0V") (class "Default")
      (node (ref "C35") (pin "2") (pinfunction "2_2") (pintype "passive"))
      (node (ref "C38") (pin "1") (pinfunction "1_1") (pintype "passive"))
      (node (ref "C44") (pin "1") (pinfunction "1_1") (pintype "passive"))
      (node (ref "C5") (pin "2") (pinfunction "2_2") (pintype "passive"))
      (node (ref "C7") (pin "1") (pinfunction "1_1") (pintype "passive"))
      (node (ref "JP3") (pin "1") (pinfunction "1_1") (pintype "passive"))
      (node (ref "JP3") (pin "2") (pinfunction "2_2") (pintype "passive"))
      (node (ref "JP3") (pin "31") (pinfunction "31_31") (pintype "passive"))
      (node (ref "JP3") (pin "32") (pinfunction "32_32") (pintype "passive"))
      (node (ref "Q3") (pin "3") (pinfunction "D_3") (pintype "passive"))
      (node (ref "R1") (pin "1") (pinfunction "1_1") (pintype "passive"))
      (node (ref "R15") (pin "6") (pinfunction "2_6") (pintype "passive"))
      (node (ref "R15") (pin "8") (pinfunction "2_8") (pintype "passive"))
      (node (ref "SJ1") (pin "3") (pinfunction "3_3") (pintype "passive"))
      (node (ref "T1") (pin "2") (pinfunction "S_2") (pintype "passive"))
      (node (ref "U2") (pin "1") (pinfunction "IN_1") (pintype "input"))
      (node (ref "U2") (pin "3") (pinfunction "ON/~{OFF}_3") (pintype "input"))
      (node (ref "U4") (pin "21") (pinfunction "SPKVDD_21") (pintype "power_in"))
      (node (ref "U4") (pin "24") (pinfunction "SPKVDD_24") (pintype "power_in"))
      (node (ref "U5") (pin "1") (pinfunction "IN_1") (pintype "power_in"))
      (node (ref "U5") (pin "3") (pinfunction "EN_3") (pintype "input"))
      (node (ref "X7") (pin "18") (pinfunction "+5V_18") (pintype "power_in"))
    )
    (net (code "5") (name "A0") (class "Default")
      (node (ref "D2") (pin "C") (pinfunction "C_C") (pintype "passive"))
      (node (ref "R38") (pin "2") (pinfunction "2_2") (pintype "passive"))
      (node (ref "X4") (pin "49") (pinfunction "GPIO40/ADC0/MISO1/TX1/SDA0/PWM8A_49") (pintype "bidirectional"))
    )
    (net (code "6") (name "A0_JST1") (class "Default")
      (node (ref "R38") (pin "1") (pinfunction "1_1") (pintype "passive"))
      (node (ref "SENSE1") (pin "3") (pinfunction "3_3") (pintype "passive"))
    )
    (net (code "7") (name "A1") (class "Default")
      (node (ref "JP3") (pin "25") (pinfunction "25_25") (pintype "passive"))
      (node (ref "X4") (pin "52") (pinfunction "GPIO41/ADC1/CS1/TX1/SCL0/PWM8B_52") (pintype "bidirectional"))
    )
    (net (code "8") (name "A2") (class "Default")
      (node (ref "JP3") (pin "23") (pinfunction "23_23") (pintype "passive"))
      (node (ref "X4") (pin "53") (pinfunction "GPIO42/ADC2/SCK1/CTS1/SDA1/PWM9A_53") (pintype "bidirectional"))
    )
    (net (code "9") (name "A3") (class "Default")
      (node (ref "JP3") (pin "21") (pinfunction "21_21") (pintype "passive"))
      (node (ref "X4") (pin "54") (pinfunction "GPIO43/ADC3/MOSI1/RTS1/SCL1/PWM9B_54") (pintype "bidirectional"))
    )
    (net (code "10") (name "A4") (class "Default")
      (node (ref "JP3") (pin "19") (pinfunction "19_19") (pintype "passive"))
      (node (ref "X4") (pin "55") (pinfunction "GPIO44/ADC4/MISO1/TX0/SDA0/PWM10A_55") (pintype "bidirectional"))
    )
    (net (code "11") (name "A5") (class "Default")
      (node (ref "JP3") (pin "17") (pinfunction "17_17") (pintype "passive"))
      (node (ref "X4") (pin "56") (pinfunction "GPIO45/ADC5/CS1/RX0/SCL0/PWM10B_56") (pintype "bidirectional"))
    )
    (net (code "12") (name "ADC_AVDD") (class "Default")
      (node (ref "C1") (pin "1") (pinfunction "1_1") (pintype "passive"))
      (node (ref "R4") (pin "1") (pinfunction "1_1") (pintype "passive"))
      (node (ref "X4") (pin "59") (pinfunction "ADC_AVDD_59") (pintype "power_in"))
    )
    (net (code "13") (name "BUTTON2") (class "Default")
      (node (ref "BTN3") (pin "A") (pinfunction "P_A") (pintype "passive"))
      (node (ref "BTN3") (pin "A'") (pinfunction "P1_A'") (pintype "passive"))
      (node (ref "X4") (pin "1") (pinfunction "MISO0/TX1/SDA0/PWM2A/GPIO4_1") (pintype "bidirectional"))
    )
    (net (code "14") (name "BUTTON3") (class "Default")
      (node (ref "BTN2") (pin "A") (pinfunction "P_A") (pintype "passive"))
      (node (ref "BTN2") (pin "A'") (pinfunction "P1_A'") (pintype "passive"))
      (node (ref "X4") (pin "2") (pinfunction "CS0/RX1/SCL0/PWM2B/GPIO5_2") (pintype "bidirectional"))
    )
    (net (code "15") (name "CC1") (class "Default")
      (node (ref "R20") (pin "2") (pinfunction "2_2") (pintype "passive"))
      (node (ref "X3") (pin "A5") (pinfunction "CC1_A5") (pintype "bidirectional"))
    )
    (net (code "16") (name "CC2") (class "Default")
      (node (ref "R19") (pin "2") (pinfunction "2_2") (pintype "passive"))
      (node (ref "X3") (pin "B5") (pinfunction "CC2_B5") (pintype "bidirectional"))
    )
    (net (code "17") (name "D+") (class "Default")
      (node (ref "R25") (pin "2") (pinfunction "2_2") (pintype "passive"))
      (node (ref "X4") (pin "67") (pinfunction "USB_D+_67") (pintype "bidirectional"))
    )
    (net (code "18") (name "D+1") (class "Default")
      (node (ref "X2") (pin "D+") (pinfunction "D+_D+") (pintype "bidirectional"))
      (node (ref "X6") (pin "12") (pinfunction "D+1_12") (pintype "bidirectional"))
    )
    (net (code "19") (name "D+2") (class "Default")
      (node (ref "X5") (pin "D+") (pinfunction "D+_D+") (pintype "bidirectional"))
      (node (ref "X6") (pin "10") (pinfunction "D+2_10") (pintype "bidirectional"))
    )
    (net (code "20") (name "D+3") (class "Default")
      (node (ref "JP3") (pin "16") (pinfunction "16_16") (pintype "passive"))
      (node (ref "X6") (pin "8") (pinfunction "D+3_8") (pintype "bidirectional"))
    )
    (net (code "21") (name "D-") (class "Default")
      (node (ref "R24") (pin "2") (pinfunction "2_2") (pintype "passive"))
      (node (ref "X4") (pin "66") (pinfunction "USB_D-_66") (pintype "bidirectional"))
    )
    (net (code "22") (name "D-1") (class "Default")
      (node (ref "X2") (pin "D-") (pinfunction "D-_D-") (pintype "bidirectional"))
      (node (ref "X6") (pin "11") (pinfunction "D-1_11") (pintype "bidirectional"))
    )
    (net (code "23") (name "D-2") (class "Default")
      (node (ref "X5") (pin "D-") (pinfunction "D-_D-") (pintype "bidirectional"))
      (node (ref "X6") (pin "9") (pinfunction "D-2_9") (pintype "bidirectional"))
    )
    (net (code "24") (name "D-3") (class "Default")
      (node (ref "JP3") (pin "14") (pinfunction "14_14") (pintype "passive"))
      (node (ref "X6") (pin "7") (pinfunction "D-3_7") (pintype "bidirectional"))
    )
    (net (code "25") (name "D6") (class "Default")
      (node (ref "JP3") (pin "15") (pinfunction "15_15") (pintype "passive"))
      (node (ref "X4") (pin "3") (pinfunction "SCK0/CTS1/SDA1/PWM3A/GPIO6_3") (pintype "bidirectional"))
    )
    (net (code "26") (name "D7") (class "Default")
      (node (ref "JP3") (pin "13") (pinfunction "13_13") (pintype "passive"))
      (node (ref "X4") (pin "4") (pinfunction "MOSI0/RTS1/SCL1/PWM3B/GPIO7_4") (pintype "bidirectional"))
    )
    (net (code "27") (name "D8{slash}TX1") (class "Default")
      (node (ref "JP3") (pin "11") (pinfunction "11_11") (pintype "passive"))
      (node (ref "U9") (pin "30") (pinfunction "RXD0_30") (pintype "bidirectional"))
      (node (ref "X4") (pin "6") (pinfunction "XIP_CS1/MISO1/TX1/SDA0/PWM4A/GPIO8_6") (pintype "bidirectional"))
    )
    (net (code "28") (name "D9{slash}RX1") (class "Default")
      (node (ref "JP3") (pin "9") (pinfunction "9_9") (pintype "passive"))
      (node (ref "R28") (pin "1") (pinfunction "1_1") (pintype "passive"))
      (node (ref "X4") (pin "7") (pinfunction "CS1/RX1/SCL0/PWM4B/GPIO9_7") (pintype "bidirectional"))
    )
    (net (code "29") (name "D10") (class "Default")
      (node (ref "JP3") (pin "7") (pinfunction "7_7") (pintype "passive"))
      (node (ref "X4") (pin "8") (pinfunction "SCK1/CTS1/SDA1/PWM5A/GPIO10_8") (pintype "bidirectional"))
    )
    (net (code "30") (name "ESP_BUSY") (class "Default")
      (node (ref "U9") (pin "24") (pinfunction "IO18_24") (pintype "bidirectional"))
      (node (ref "X4") (pin "80") (pinfunction "MOSI0/RTS0/SCL1/PWM1B/GPIO3_80") (pintype "bidirectional"))
    )
    (net (code "31") (name "ESP_CS") (class "Default")
      (node (ref "IC1") (pin "1") (pinfunction "~{OE}_1") (pintype "input"))
      (node (ref "U9") (pin "16") (pinfunction "IO7_16") (pintype "bidirectional"))
      (node (ref "X4") (pin "57") (pinfunction "GPIO46/ADC6/SCK1/CTS0/SDA1/PWM11A_57") (pintype "bidirectional"))
    )
    (net (code "32") (name "ESP_MISO") (class "Default")
      (node (ref "IC1") (pin "2") (pinfunction "A_2") (pintype "input"))
      (node (ref "U9") (pin "15") (pinfunction "IO6/ADC1_6_15") (pintype "bidirectional"))
    )
    (net (code "33") (name "ESP_TX") (class "Default")
      (node (ref "R28") (pin "2") (pinfunction "2_2") (pintype "passive"))
      (node (ref "U9") (pin "31") (pinfunction "TXD0_31") (pintype "bidirectional"))
    )
    (net (code "34") (name "GND") (class "Default")
      (node (ref "BTN0") (pin "A") (pinfunction "P_A") (pintype "passive"))
      (node (ref "BTN0") (pin "A'") (pinfunction "P1_A'") (pintype "passive"))
      (node (ref "BTN2") (pin "B") (pinfunction "S_B") (pintype "passive"))
      (node (ref "BTN2") (pin "B'") (pinfunction "S1_B'") (pintype "passive"))
      (node (ref "BTN3") (pin "B") (pinfunction "S_B") (pintype "passive"))
      (node (ref "BTN3") (pin "B'") (pinfunction "S1_B'") (pintype "passive"))
      (node (ref "C1") (pin "2") (pinfunction "2_2") (pintype "passive"))
      (node (ref "C10") (pin "2") (pinfunction "2_2") (pintype "passive"))
      (node (ref "C11") (pin "2") (pinfunction "2_2") (pintype "passive"))
      (node (ref "C12") (pin "2") (pinfunction "2_2") (pintype "passive"))
      (node (ref "C13") (pin "2") (pinfunction "2_2") (pintype "passive"))
      (node (ref "C14") (pin "1") (pinfunction "1_1") (pintype "passive"))
      (node (ref "C15") (pin "1") (pinfunction "1_1") (pintype "passive"))
      (node (ref "C16") (pin "2") (pinfunction "2_2") (pintype "passive"))
      (node (ref "C17") (pin "2") (pinfunction "2_2") (pintype "passive"))
      (node (ref "C18") (pin "2") (pinfunction "2_2") (pintype "passive"))
      (node (ref "C19") (pin "2") (pinfunction "2_2") (pintype "passive"))
      (node (ref "C2") (pin "2") (pinfunction "2_2") (pintype "passive"))
      (node (ref "C20") (pin "2") (pinfunction "2_2") (pintype "passive"))
      (node (ref "C21") (pin "2") (pinfunction "2_2") (pintype "passive"))
      (node (ref "C22") (pin "2") (pinfunction "2_2") (pintype "passive"))
      (node (ref "C23") (pin "2") (pinfunction "2_2") (pintype "passive"))
      (node (ref "C24") (pin "2") (pinfunction "2_2") (pintype "passive"))
      (node (ref "C25") (pin "2") (pinfunction "2_2") (pintype "passive"))
      (node (ref "C26") (pin "1") (pinfunction "1_1") (pintype "passive"))
      (node (ref "C27") (pin "1") (pinfunction "1_1") (pintype "passive"))
      (node (ref "C28") (pin "2") (pinfunction "2_2") (pintype "passive"))
      (node (ref "C29") (pin "2") (pinfunction "2_2") (pintype "passive"))
      (node (ref "C3") (pin "1") (pinfunction "1_1") (pintype "passive"))
      (node (ref "C30") (pin "2") (pinfunction "2_2") (pintype "passive"))
      (node (ref "C31") (pin "2") (pinfunction "2_2") (pintype "passive"))
      (node (ref "C32") (pin "1") (pinfunction "1_1") (pintype "passive"))
      (node (ref "C33") (pin "1") (pinfunction "1_1") (pintype "passive"))
      (node (ref "C34") (pin "2") (pinfunction "2_2") (pintype "passive"))
      (node (ref "C35") (pin "1") (pinfunction "1_1") (pintype "passive"))
      (node (ref "C36") (pin "2") (pinfunction "2_2") (pintype "passive"))
      (node (ref "C37") (pin "2") (pinfunction "2_2") (pintype "passive"))
      (node (ref "C38") (pin "2") (pinfunction "2_2") (pintype "passive"))
      (node (ref "C39") (pin "2") (pinfunction "2_2") (pintype "passive"))
      (node (ref "C4") (pin "2") (pinfunction "2_2") (pintype "passive"))
      (node (ref "C40") (pin "2") (pinfunction "2_2") (pintype "passive"))
      (node (ref "C41") (pin "2") (pinfunction "2_2") (pintype "passive"))
      (node (ref "C44") (pin "2") (pinfunction "2_2") (pintype "passive"))
      (node (ref "C45") (pin "2") (pinfunction "2_2") (pintype "passive"))
      (node (ref "C46") (pin "1") (pinfunction "1_1") (pintype "passive"))
      (node (ref "C48") (pin "2") (pinfunction "2_2") (pintype "passive"))
      (node (ref "C5") (pin "1") (pinfunction "1_1") (pintype "passive"))
      (node (ref "C50") (pin "2") (pinfunction "2_2") (pintype "passive"))
      (node (ref "C53") (pin "2") (pinfunction "2_2") (pintype "passive"))
      (node (ref "C54") (pin "2") (pinfunction "2_2") (pintype "passive"))
      (node (ref "C55") (pin "2") (pinfunction "2_2") (pintype "passive"))
      (node (ref "C6") (pin "1") (pinfunction "1_1") (pintype "passive"))
      (node (ref "C7") (pin "2") (pinfunction "2_2") (pintype "passive"))
      (node (ref "C8") (pin "1") (pinfunction "1_1") (pintype "passive"))
      (node (ref "C9") (pin "2") (pinfunction "2_2") (pintype "passive"))
      (node (ref "CONN1") (pin "1") (pinfunction "GND_1") (pintype "passive"))
      (node (ref "CONN1") (pin "MT1") (pinfunction "MT_MT1") (pintype "bidirectional"))
      (node (ref "CONN1") (pin "MT2") (pinfunction "MT_MT2") (pintype "bidirectional"))
      (node (ref "D2") (pin "A") (pinfunction "A_A") (pintype "passive"))
      (node (ref "DEBUG") (pin "2") (pinfunction "2_2") (pintype "passive"))
      (node (ref "DEBUG") (pin "MT1") (pinfunction "MT_MT1") (pintype "bidirectional"))
      (node (ref "DEBUG") (pin "MT2") (pinfunction "MT_MT2") (pintype "bidirectional"))
      (node (ref "IC1") (pin "3") (pinfunction "GND_3") (pintype "power_in"))
      (node (ref "JP3") (pin "27") (pinfunction "27_27") (pintype "passive"))
      (node (ref "JP3") (pin "28") (pinfunction "28_28") (pintype "passive"))
      (node (ref "JP3") (pin "5") (pinfunction "5_5") (pintype "passive"))
      (node (ref "JP3") (pin "6") (pinfunction "6_6") (pintype "passive"))
      (node (ref "LED1") (pin "4") (pinfunction "GND_4") (pintype "power_in"))
      (node (ref "LED2") (pin "4") (pinfunction "GND_4") (pintype "power_in"))
      (node (ref "LED3") (pin "4") (pinfunction "GND_4") (pintype "power_in"))
      (node (ref "LED4") (pin "4") (pinfunction "GND_4") (pintype "power_in"))
      (node (ref "LED5") (pin "4") (pinfunction "GND_4") (pintype "power_in"))
      (node (ref "O1") (pin "1") (pinfunction "GND_1") (pintype "power_in"))
      (node (ref "O1") (pin "2") (pinfunction "GND_2") (pintype "power_in"))
      (node (ref "ON") (pin "C") (pinfunction "C_C") (pintype "passive"))
      (node (ref "Q1") (pin "2") (pinfunction "S_2") (pintype "bidirectional"))
      (node (ref "R18") (pin "1") (pinfunction "1_1") (pintype "passive"))
      (node (ref "R19") (pin "1") (pinfunction "1_1") (pintype "passive"))
      (node (ref "R20") (pin "1") (pinfunction "1_1") (pintype "passive"))
      (node (ref "R8") (pin "1") (pinfunction "1_1") (pintype "passive"))
      (node (ref "SENSE1") (pin "1") (pinfunction "1_1") (pintype "passive"))
      (node (ref "SENSE1") (pin "NC1") (pinfunction "MT_NC1") (pintype "bidirectional"))
      (node (ref "SENSE1") (pin "NC2") (pinfunction "MT_NC2") (pintype "bidirectional"))
      (node (ref "SW1") (pin "A") (pinfunction "P_A") (pintype "passive"))
      (node (ref "SW1") (pin "A'") (pinfunction "P1_A'") (pintype "passive"))
      (node (ref "SW2") (pin "MNT1") (pinfunction "MT_MNT1") (pintype "bidirectional"))
      (node (ref "SW2") (pin "MNT2") (pinfunction "MT_MNT2") (pintype "bidirectional"))
      (node (ref "SW2") (pin "T1") (pinfunction "O_T1") (pintype "passive"))
      (node (ref "TP2") (pin "P$1") (pinfunction "SEW_P$1") (pintype "bidirectional"))
      (node (ref "TP3") (pin "P$1") (pinfunction "SEW_P$1") (pintype "bidirectional"))
      (node (ref "TP4") (pin "P$1") (pinfunction "SEW_P$1") (pintype "bidirectional"))
      (node (ref "TP5") (pin "P$1") (pinfunction "SEW_P$1") (pintype "bidirectional"))
      (node (ref "U2") (pin "2") (pinfunction "GND_2") (pintype "power_in"))
      (node (ref "U3") (pin "4") (pinfunction "VSS_4") (pintype "bidirectional"))
      (node (ref "U4") (pin "1") (pinfunction "IOVSS_1") (pintype "power_in"))
      (node (ref "U4") (pin "13") (pinfunction "AIN1_13") (pintype "input"))
      (node (ref "U4") (pin "14") (pinfunction "AIN2_14") (pintype "input"))
      (node (ref "U4") (pin "16") (pinfunction "AVSS_16") (pintype "power_in"))
      (node (ref "U4") (pin "18") (pinfunction "DVSS_18") (pintype "power_in"))
      (node (ref "U4") (pin "20") (pinfunction "SPKVSS_20") (pintype "power_in"))
      (node (ref "U4") (pin "25") (pinfunction "SPKVSS_25") (pintype "power_in"))
      (node (ref "U4") (pin "29") (pinfunction "HPVSS_29") (pintype "power_in"))
      (node (ref "U4") (pin "33") (pinfunction "EP_33") (pintype "bidirectional"))
      (node (ref "U5") (pin "2") (pinfunction "GND_2") (pintype "power_in"))
      (node (ref "U6") (pin "4") (pinfunction "VSS_4") (pintype "bidirectional"))
      (node (ref "U9") (pin "1") (pinfunction "GND_1") (pintype "power_in"))
      (node (ref "U9") (pin "11") (pinfunction "GND_11") (pintype "power_in"))
      (node (ref "U9") (pin "14") (pinfunction "GND_14") (pintype "power_in"))
      (node (ref "U9") (pin "2") (pinfunction "GND_2") (pintype "power_in"))
      (node (ref "U9") (pin "36") (pinfunction "GND_36") (pintype "power_in"))
      (node (ref "U9") (pin "37") (pinfunction "GND_37") (pintype "power_in"))
      (node (ref "U9") (pin "38") (pinfunction "GND_38") (pintype "power_in"))
      (node (ref "U9") (pin "39") (pinfunction "GND_39") (pintype "power_in"))
      (node (ref "U9") (pin "40") (pinfunction "GND_40") (pintype "power_in"))
      (node (ref "U9") (pin "41") (pinfunction "GND_41") (pintype "power_in"))
      (node (ref "U9") (pin "42") (pinfunction "GND_42") (pintype "power_in"))
      (node (ref "U9") (pin "43") (pinfunction "GND_43") (pintype "power_in"))
      (node (ref "U9") (pin "44") (pinfunction "GND_44") (pintype "power_in"))
      (node (ref "U9") (pin "45") (pinfunction "GND_45") (pintype "power_in"))
      (node (ref "U9") (pin "46") (pinfunction "GND_46") (pintype "power_in"))
      (node (ref "U9") (pin "47") (pinfunction "GND_47") (pintype "power_in"))
      (node (ref "U9") (pin "48") (pinfunction "GND_48") (pintype "power_in"))
      (node (ref "U9") (pin "49") (pinfunction "GND_49") (pintype "power_in"))
      (node (ref "U9") (pin "50") (pinfunction "GND_50") (pintype "power_in"))
      (node (ref "U9") (pin "51") (pinfunction "GND_51") (pintype "power_in"))
      (node (ref "U9") (pin "52") (pinfunction "GND_52") (pintype "power_in"))
      (node (ref "U9") (pin "53") (pinfunction "GND_53") (pintype "power_in"))
      (node (ref "U9") (pin "54") (pinfunction "GND_54") (pintype "power_in"))
      (node (ref "U9") (pin "55") (pinfunction "GND_55") (pintype "power_in"))
      (node (ref "U9") (pin "56") (pinfunction "GND_56") (pintype "power_in"))
      (node (ref "U9") (pin "57") (pinfunction "GND_57") (pintype "power_in"))
      (node (ref "U9") (pin "58") (pinfunction "GND_58") (pintype "power_in"))
      (node (ref "U9") (pin "59") (pinfunction "GND_59") (pintype "power_in"))
      (node (ref "U9") (pin "6") (pinfunction "IO3/ADC1_3_6") (pintype "bidirectional"))
      (node (ref "U9") (pin "60") (pinfunction "GND_60") (pintype "power_in"))
      (node (ref "U9") (pin "61") (pinfunction "GND_61") (pintype "power_in"))
      (node (ref "X1") (pin "6") (pinfunction "SD_VSS_6") (pintype "power_in"))
      (node (ref "X1") (pin "MT1") (pinfunction "MOUNTING_MT1") (pintype "passive"))
      (node (ref "X1") (pin "MT2") (pinfunction "MOUNTING_MT2") (pintype "passive"))
      (node (ref "X2") (pin "GND") (pinfunction "GND_GND") (pintype "power_in"))
      (node (ref "X2") (pin "S1") (pinfunction "MT_S1") (pintype "bidirectional"))
      (node (ref "X2") (pin "S2") (pinfunction "MT_S2") (pintype "bidirectional"))
      (node (ref "X3") (pin "A1B12") (pinfunction "GND_A1B12") (pintype "power_in"))
      (node (ref "X3") (pin "B1A12") (pinfunction "GND_B1A12") (pintype "power_in"))
      (node (ref "X4") (pin "62") (pinfunction "VREG_PGND_62") (pintype "power_in"))
      (node (ref "X4") (pin "MNT") (pinfunction "GND_MNT") (pintype "power_in"))
      (node (ref "X5") (pin "GND") (pinfunction "GND_GND") (pintype "power_in"))
      (node (ref "X5") (pin "S1") (pinfunction "MT_S1") (pintype "bidirectional"))
      (node (ref "X5") (pin "S2") (pinfunction "MT_S2") (pintype "bidirectional"))
      (node (ref "X6") (pin "THERM") (pinfunction "GND_THERM") (pintype "power_in"))
      (node (ref "X7") (pin "11") (pinfunction "TXC_SHIELD_11") (pintype "power_in"))
      (node (ref "X7") (pin "17") (pinfunction "GND_17") (pintype "power_in"))
      (node (ref "X7") (pin "2") (pinfunction "TX2_SHIELD_2") (pintype "power_in"))
      (node (ref "X7") (pin "5") (pinfunction "TX1_SHIELD_5") (pintype "power_in"))
      (node (ref "X7") (pin "8") (pinfunction "TX0_SHIELD_8") (pintype "power_in"))
      (node (ref "X8") (pin "2") (pinfunction "RING1_2") (pintype "passive"))
    )
    (net (code "35") (name "HDMI_TX0+") (class "Default")
      (node (ref "R14") (pin "4") (pinfunction "1_4") (pintype "passive"))
      (node (ref "X7") (pin "7") (pinfunction "TX0+_7") (pintype "bidirectional"))
    )
    (net (code "36") (name "HDMI_TX0-") (class "Default")
      (node (ref "R14") (pin "3") (pinfunction "1_3") (pintype "passive"))
      (node (ref "X7") (pin "9") (pinfunction "TX0-_9") (pintype "bidirectional"))
    )
    (net (code "37") (name "HDMI_TX1+") (class "Default")
      (node (ref "R12") (pin "2") (pinfunction "1_2") (pintype "passive"))
      (node (ref "X7") (pin "4") (pinfunction "TX1+_4") (pintype "bidirectional"))
    )
    (net (code "38") (name "HDMI_TX1-") (class "Default")
      (node (ref "R12") (pin "1") (pinfunction "1_1") (pintype "passive"))
      (node (ref "X7") (pin "6") (pinfunction "TX1-_6") (pintype "bidirectional"))
    )
    (net (code "39") (name "HDMI_TX2+") (class "Default")
      (node (ref "R12") (pin "4") (pinfunction "1_4") (pintype "passive"))
      (node (ref "X7") (pin "1") (pinfunction "TX2+_1") (pintype "bidirectional"))
    )
    (net (code "40") (name "HDMI_TX2-") (class "Default")
      (node (ref "R12") (pin "3") (pinfunction "1_3") (pintype "passive"))
      (node (ref "X7") (pin "3") (pinfunction "TX2-_3") (pintype "bidirectional"))
    )
    (net (code "41") (name "HDMI_TXC+") (class "Default")
      (node (ref "R14") (pin "2") (pinfunction "1_2") (pintype "passive"))
      (node (ref "X7") (pin "10") (pinfunction "TXC+_10") (pintype "bidirectional"))
    )
    (net (code "42") (name "HDMI_TXC-") (class "Default")
      (node (ref "R14") (pin "1") (pinfunction "1_1") (pintype "passive"))
      (node (ref "X7") (pin "12") (pinfunction "TXC-_12") (pintype "bidirectional"))
    )
    (net (code "43") (name "HOTPLUG") (class "Default")
      (node (ref "R16") (pin "1") (pinfunction "1_1") (pintype "passive"))
      (node (ref "X7") (pin "19") (pinfunction "HOTPLUG_19") (pintype "bidirectional"))
    )
    (net (code "44") (name "HOTPLUG_3V") (class "Default")
      (node (ref "R16") (pin "2") (pinfunction "2_2") (pintype "passive"))
      (node (ref "R18") (pin "2") (pinfunction "2_2") (pintype "passive"))
    )
    (net (code "45") (name "HSTX12") (class "Default")
      (node (ref "R14") (pin "8") (pinfunction "2_8") (pintype "passive"))
      (node (ref "X4") (pin "11") (pinfunction "HSTX/MISO1/TX0/SDA0/PWM6A/GPIO12_11") (pintype "bidirectional"))
    )
    (net (code "46") (name "HSTX13") (class "Default")
      (node (ref "R14") (pin "7") (pinfunction "2_7") (pintype "passive"))
      (node (ref "X4") (pin "12") (pinfunction "HSTX/CS1/RX0/SCL0/PWM6B/GPIO13_12") (pintype "bidirectional"))
    )
    (net (code "47") (name "HSTX14") (class "Default")
      (node (ref "R14") (pin "6") (pinfunction "2_6") (pintype "passive"))
      (node (ref "X4") (pin "13") (pinfunction "HSTX/SCK1/CTS0/SDA1/PWM7A/GPIO14_13") (pintype "bidirectional"))
    )
    (net (code "48") (name "HSTX15") (class "Default")
      (node (ref "R14") (pin "5") (pinfunction "2_5") (pintype "passive"))
      (node (ref "X4") (pin "14") (pinfunction "HSTX/MOSI1/RTS0/SCL1/PWM7B/GPIO15_14") (pintype "bidirectional"))
    )
    (net (code "49") (name "HSTX16") (class "Default")
      (node (ref "R12") (pin "8") (pinfunction "2_8") (pintype "passive"))
      (node (ref "X4") (pin "16") (pinfunction "HSTX/MISO0/TX0/SDA0/PWM0A/GPIO16_16") (pintype "bidirectional"))
    )
    (net (code "50") (name "HSTX17") (class "Default")
      (node (ref "R12") (pin "7") (pinfunction "2_7") (pintype "passive"))
      (node (ref "X4") (pin "17") (pinfunction "HSTX/CS0/RX0/SCL0/PWM0B/GPIO17_17") (pintype "bidirectional"))
    )
    (net (code "51") (name "HSTX18") (class "Default")
      (node (ref "R12") (pin "6") (pinfunction "2_6") (pintype "passive"))
      (node (ref "X4") (pin "18") (pinfunction "HSTX/SCK0/CTS0/SDA1/PWM1A/GPIO18_18") (pintype "bidirectional"))
    )
    (net (code "52") (name "HSTX19") (class "Default")
      (node (ref "R12") (pin "5") (pinfunction "2_5") (pintype "passive"))
      (node (ref "X4") (pin "19") (pinfunction "XPI_CS1/HSTX/MOSI0/RTS0/SCL1/PWM1B/GPIO19_19") (pintype "bidirectional"))
    )
    (net (code "53") (name "I2S_BCLK") (class "Default")
      (node (ref "U4") (pin "7") (pinfunction "BCLK_7") (pintype "input"))
      (node (ref "X4") (pin "27") (pinfunction "SCK1/CTS1/SDA1/PWM5A/GPIO26_27") (pintype "bidirectional"))
    )
    (net (code "54") (name "I2S_DIN") (class "Default")
      (node (ref "U4") (pin "5") (pinfunction "DIN_5") (pintype "input"))
      (node (ref "X4") (pin "25") (pinfunction "MISO1/TX1/SDA0/PWM4A/GPIO24_25") (pintype "bidirectional"))
    )
    (net (code "55") (name "I2S_ESP_IRQ") (class "Default")
      (node (ref "ESP_BOOT") (pin "1") (pinfunction "1_1") (pintype "passive"))
      (node (ref "R27") (pin "1") (pinfunction "1_1") (pintype "passive"))
      (node (ref "U4") (pin "32") (pinfunction "GPIO1_32") (pintype "bidirectional"))
      (node (ref "U9") (pin "23") (pinfunction "IO9/BOOT9_23") (pintype "bidirectional"))
      (node (ref "X4") (pin "23") (pinfunction "MOSI0/RTS1/SCL1/PWM3B/GPIO23_23") (pintype "bidirectional"))
    )
    (net (code "56") (name "I2S_LRCLK") (class "Default")
      (node (ref "U4") (pin "6") (pinfunction "WCLK_6") (pintype "input"))
      (node (ref "X4") (pin "28") (pinfunction "MOSI1/RTS1/SCL1/PWM5B/GPIO27_28") (pintype "bidirectional"))
    )
    (net (code "57") (name "I2S_MCLK") (class "Default")
      (node (ref "U4") (pin "8") (pinfunction "MCLK_8") (pintype "input"))
      (node (ref "X4") (pin "26") (pinfunction "CS1/RX1/SCL0/PWM4B/GPIO25_26") (pintype "bidirectional"))
    )
    (net (code "58") (name "IRIN") (class "Default")
      (node (ref "O1") (pin "3") (pinfunction "OUT_3") (pintype "output"))
      (node (ref "R32") (pin "2") (pinfunction "2_2") (pintype "passive"))
    )
    (net (code "59") (name "LED") (class "Default")
      (node (ref "R11") (pin "1") (pinfunction "1_1") (pintype "passive"))
      (node (ref "R32") (pin "1") (pinfunction "1_1") (pintype "passive"))
      (node (ref "X4") (pin "37") (pinfunction "CS1/RX0/SCL0/PWM6B/GPIO29_37") (pintype "bidirectional"))
    )
    (net (code "60") (name "LX") (class "Default")
      (node (ref "L1") (pin "P$2") (pinfunction "2_P$2") (pintype "passive"))
      (node (ref "X4") (pin "63") (pinfunction "VREG_LX_63") (pintype "input"))
    )
    (net (code "61") (name "MICDET") (class "Default")
      (node (ref "R22") (pin "1") (pinfunction "1_1") (pintype "passive"))
      (node (ref "U4") (pin "11") (pinfunction "VOL/MICDET_11") (pintype "input"))
      (node (ref "X8") (pin "1") (pinfunction "RING_1") (pintype "passive"))
    )
    (net (code "62") (name "MISO") (class "Default")
      (node (ref "IC1") (pin "4") (pinfunction "Y_4") (pintype "output"))
      (node (ref "JP3") (pin "20") (pinfunction "20_20") (pintype "passive"))
      (node (ref "X4") (pin "36") (pinfunction "MISO1/TX0/SDA0/PWM6A/GPIO28_36") (pintype "bidirectional"))
    )
    (net (code "63") (name "MISO{slash}SDIO_DAT0") (class "Default")
      (node (ref "X1") (pin "7") (pinfunction "DATA_OUT_7") (pintype "output"))
      (node (ref "X4") (pin "45") (pinfunction "GPIO36/MISO0/TX1/SDA0/PWM10A_45") (pintype "bidirectional"))
    )
    (net (code "64") (name "MOSI") (class "Default")
      (node (ref "JP3") (pin "18") (pinfunction "18_18") (pintype "passive"))
      (node (ref "U9") (pin "27") (pinfunction "IO21_27") (pintype "bidirectional"))
      (node (ref "X4") (pin "39") (pinfunction "MOSI1/RTS0/SCL1/PWM7B/GPIO31_39") (pintype "bidirectional"))
    )
    (net (code "65") (name "MOSI{slash}SDIO_CMD") (class "Default")
      (node (ref "X1") (pin "3") (pinfunction "DATA_IN_3") (pintype "input"))
      (node (ref "X4") (pin "44") (pinfunction "GPIO35/MOSI0/RTS0/SCL1/PWM9B_44") (pintype "bidirectional"))
    )
    (net (code "66") (name "NEOPIX") (class "Default")
      (node (ref "LED2") (pin "1") (pinfunction "DI_1") (pintype "input"))
      (node (ref "X4") (pin "40") (pinfunction "GPIO32/MISO0/TX0/SDA0/PWM8A_40") (pintype "bidirectional"))
    )
    (net (code "67") (name "Net-(D3-PadA)") (class "Default")
      (node (ref "D3") (pin "A") (pinfunction "A_A") (pintype "passive"))
      (node (ref "R26") (pin "2") (pinfunction "2_2") (pintype "passive"))
    )
    (net (code "68") (name "Net-(L-PadC)") (class "Default")
      (node (ref "L") (pin "C") (pinfunction "C_C") (pintype "passive"))
      (node (ref "R11") (pin "2") (pinfunction "2_2") (pintype "passive"))
    )
    (net (code "69") (name "Net-(LED1-DI)") (class "Default")
      (node (ref "LED1") (pin "1") (pinfunction "DI_1") (pintype "input"))
      (node (ref "LED2") (pin "3") (pinfunction "DO_3") (pintype "output"))
    )
    (net (code "70") (name "Net-(LED1-DO)") (class "Default")
      (node (ref "LED1") (pin "3") (pinfunction "DO_3") (pintype "output"))
      (node (ref "LED3") (pin "1") (pinfunction "DI_1") (pintype "input"))
    )
    (net (code "71") (name "Net-(LED3-DO)") (class "Default")
      (node (ref "LED3") (pin "3") (pinfunction "DO_3") (pintype "output"))
      (node (ref "LED4") (pin "1") (pinfunction "DI_1") (pintype "input"))
    )
    (net (code "72") (name "Net-(LED4-DO)") (class "Default")
      (node (ref "LED4") (pin "3") (pinfunction "DO_3") (pintype "output"))
      (node (ref "LED5") (pin "1") (pinfunction "DI_1") (pintype "input"))
    )
    (net (code "73") (name "Net-(ON-PadA)") (class "Default")
      (node (ref "ON") (pin "A") (pinfunction "A_A") (pintype "passive"))
      (node (ref "R2") (pin "2") (pinfunction "2_2") (pintype "passive"))
    )
    (net (code "74") (name "Net-(P1LED-PadA)") (class "Default")
      (node (ref "P1LED") (pin "A") (pinfunction "A_A") (pintype "passive"))
      (node (ref "P2LED") (pin "C") (pinfunction "C_C") (pintype "passive"))
      (node (ref "R9") (pin "2") (pinfunction "2_2") (pintype "passive"))
    )
    (net (code "75") (name "Net-(Q1-D)") (class "Default")
      (node (ref "Q1") (pin "3") (pinfunction "D_3") (pintype "bidirectional"))
      (node (ref "R1") (pin "2") (pinfunction "2_2") (pintype "passive"))
      (node (ref "T1") (pin "1") (pinfunction "G_1") (pintype "passive"))
    )
    (net (code "76") (name "Net-(Q3-G)") (class "Default")
      (node (ref "Q3") (pin "1") (pinfunction "G_1") (pintype "passive"))
      (node (ref "R10") (pin "1") (pinfunction "1_1") (pintype "passive"))
      (node (ref "SW2") (pin "P") (pinfunction "P_P") (pintype "passive"))
    )
    (net (code "77") (name "Net-(T1-D)") (class "Default")
      (node (ref "PTC1") (pin "2") (pinfunction "2_2") (pintype "passive"))
      (node (ref "T1") (pin "3") (pinfunction "D_3") (pintype "passive"))
    )
    (net (code "78") (name "Net-(U4-HPL)") (class "Default")
      (node (ref "C42") (pin "1") (pinfunction "1_1") (pintype "passive"))
      (node (ref "U4") (pin "27") (pinfunction "HPL_27") (pintype "output"))
    )
    (net (code "79") (name "Net-(U4-HPR)") (class "Default")
      (node (ref "C43") (pin "1") (pinfunction "1_1") (pintype "passive"))
      (node (ref "U4") (pin "30") (pinfunction "HPR_30") (pintype "output"))
    )
    (net (code "80") (name "Net-(U4-MICBIAS)") (class "Default")
      (node (ref "R22") (pin "2") (pinfunction "2_2") (pintype "passive"))
      (node (ref "U4") (pin "12") (pinfunction "MICBIAS_12") (pintype "output"))
    )
    (net (code "81") (name "Net-(X6-LED2)") (class "Default")
      (node (ref "R9") (pin "1") (pinfunction "1_1") (pintype "passive"))
      (node (ref "X6") (pin "23") (pinfunction "LED2_23") (pintype "bidirectional"))
    )
    (net (code "82") (name "Net-(X6-LED4{slash}SDA)") (class "Default")
      (node (ref "P1LED") (pin "C") (pinfunction "C_C") (pintype "passive"))
      (node (ref "P2LED") (pin "A") (pinfunction "A_A") (pintype "passive"))
      (node (ref "X6") (pin "21") (pinfunction "LED4/SDA_21") (pintype "bidirectional"))
    )
    (net (code "83") (name "Net-(X6-XIN)") (class "Default")
      (node (ref "X6") (pin "4") (pinfunction "XIN_4") (pintype "input"))
      (node (ref "Y2") (pin "3") (pinfunction "2_3") (pintype "passive"))
    )
    (net (code "84") (name "Net-(X6-XOUT)") (class "Default")
      (node (ref "X6") (pin "3") (pinfunction "XOUT_3") (pintype "output"))
      (node (ref "Y2") (pin "1") (pinfunction "1_1") (pintype "passive"))
    )
    (net (code "85") (name "Net-(Y1-2)") (class "Default")
      (node (ref "C27") (pin "2") (pinfunction "2_2") (pintype "passive"))
      (node (ref "R23") (pin "1") (pinfunction "1_1") (pintype "passive"))
      (node (ref "Y1") (pin "3") (pinfunction "2_3") (pintype "passive"))
    )
    (net (code "86") (name "OUTL") (class "Default")
      (node (ref "C42") (pin "2") (pinfunction "2_2") (pintype "passive"))
      (node (ref "X8") (pin "4") (pinfunction "TIP_4") (pintype "passive"))
      (node (ref "X8") (pin "6") (pinfunction "TIP_SW_6") (pintype "passive"))
    )
    (net (code "87") (name "OUTR") (class "Default")
      (node (ref "C43") (pin "2") (pinfunction "2_2") (pintype "passive"))
      (node (ref "X8") (pin "3") (pinfunction "RING2_3") (pintype "passive"))
      (node (ref "X8") (pin "5") (pinfunction "R2_SW_5") (pintype "passive"))
    )
    (net (code "88") (name "PERIPH_RST") (class "Default")
      (node (ref "JP3") (pin "24") (pinfunction "24_24") (pintype "passive"))
      (node (ref "R13") (pin "1") (pinfunction "1_1") (pintype "passive"))
      (node (ref "R7") (pin "1") (pinfunction "1_1") (pintype "passive"))
      (node (ref "U4") (pin "31") (pinfunction "~{RESET}_31") (pintype "input"))
      (node (ref "U9") (pin "8") (pinfunction "EN_8") (pintype "input"))
      (node (ref "X4") (pin "22") (pinfunction "SCK0/CTS1/SDA1/PWM3A/GPIO22_22") (pintype "bidirectional"))
    )
    (net (code "89") (name "PSRAM_CS") (class "Default")
      (node (ref "R6") (pin "1") (pinfunction "1_1") (pintype "passive"))
      (node (ref "U3") (pin "1") (pinfunction "SSEL_1") (pintype "bidirectional"))
      (node (ref "X4") (pin "58") (pinfunction "GPIO47/ADC7/MOSI1/RTS0/SCL1/PWM11B_58") (pintype "bidirectional"))
    )
    (net (code "90") (name "QSPI_CS") (class "Default")
      (node (ref "R17") (pin "1") (pinfunction "1_1") (pintype "passive"))
      (node (ref "R26") (pin "1") (pinfunction "1_1") (pintype "passive"))
      (node (ref "U6") (pin "1") (pinfunction "SSEL_1") (pintype "bidirectional"))
      (node (ref "X4") (pin "75") (pinfunction "~{QSPI_CS}_75") (pintype "bidirectional"))
    )
    (net (code "91") (name "QSPI_DATA[0]") (class "Default")
      (node (ref "U3") (pin "5") (pinfunction "MOSI_5") (pintype "bidirectional"))
      (node (ref "U6") (pin "5") (pinfunction "MOSI_5") (pintype "bidirectional"))
      (node (ref "X4") (pin "72") (pinfunction "QSPI_SD0_72") (pintype "bidirectional"))
    )
    (net (code "92") (name "QSPI_DATA[1]") (class "Default")
      (node (ref "U3") (pin "2") (pinfunction "MISO_2") (pintype "bidirectional"))
      (node (ref "U6") (pin "2") (pinfunction "MISO_2") (pintype "bidirectional"))
      (node (ref "X4") (pin "74") (pinfunction "QSPI_SD1_74") (pintype "bidirectional"))
    )
    (net (code "93") (name "QSPI_DATA[2]") (class "Default")
      (node (ref "U3") (pin "3") (pinfunction "WP#/IO2_3") (pintype "bidirectional"))
      (node (ref "U6") (pin "3") (pinfunction "WP#/IO2_3") (pintype "bidirectional"))
      (node (ref "X4") (pin "73") (pinfunction "QSPI_SD2_73") (pintype "bidirectional"))
    )
    (net (code "94") (name "QSPI_DATA[3]") (class "Default")
      (node (ref "U3") (pin "7") (pinfunction "HOLD#/IO3_7") (pintype "bidirectional"))
      (node (ref "U6") (pin "7") (pinfunction "HOLD#/IO3_7") (pintype "bidirectional"))
      (node (ref "X4") (pin "70") (pinfunction "QSPI_SD3_70") (pintype "bidirectional"))
    )
    (net (code "95") (name "QSPI_SCK") (class "Default")
      (node (ref "U3") (pin "6") (pinfunction "SCK_6") (pintype "bidirectional"))
      (node (ref "U6") (pin "6") (pinfunction "SCK_6") (pintype "bidirectional"))
      (node (ref "X4") (pin "71") (pinfunction "QSPI_SCLK_71") (pintype "bidirectional"))
    )
    (net (code "96") (name "SCK") (class "Default")
      (node (ref "JP3") (pin "22") (pinfunction "22_22") (pintype "passive"))
      (node (ref "U9") (pin "28") (pinfunction "IO22_28") (pintype "bidirectional"))
      (node (ref "X4") (pin "38") (pinfunction "SCK1/CTS0/SDA1/PWM7A/GPIO30_38") (pintype "bidirectional"))
    )
    (net (code "97") (name "SCK{slash}SDIO_CLK") (class "Default")
      (node (ref "X1") (pin "5") (pinfunction "SCLK_5") (pintype "input"))
      (node (ref "X4") (pin "43") (pinfunction "GPIO34/SCK0/CTS0/SDA1/PWM9A_43") (pintype "bidirectional"))
    )
    (net (code "98") (name "SCL") (class "Default")
      (node (ref "CONN1") (pin "4") (pinfunction "SCL_4") (pintype "passive"))
      (node (ref "JP3") (pin "8") (pinfunction "8_8") (pintype "passive"))
      (node (ref "Q2") (pin "1") (pinfunction "S_1") (pintype "bidirectional"))
      (node (ref "R15") (pin "4") (pinfunction "1_4") (pintype "passive"))
      (node (ref "U4") (pin "10") (pinfunction "SCL_10") (pintype "input"))
      (node (ref "X4") (pin "21") (pinfunction "CS0/RX1/SCL0/PWM2B/GPIO21_21") (pintype "bidirectional"))
    )
    (net (code "99") (name "SCL_5V") (class "Default")
      (node (ref "Q2") (pin "6") (pinfunction "D_6") (pintype "bidirectional"))
      (node (ref "R15") (pin "1") (pinfunction "1_1") (pintype "passive"))
      (node (ref "X7") (pin "15") (pinfunction "DCLK_15") (pintype "bidirectional"))
    )
    (net (code "100") (name "SDA") (class "Default")
      (node (ref "CONN1") (pin "3") (pinfunction "SDA_3") (pintype "passive"))
      (node (ref "JP3") (pin "10") (pinfunction "10_10") (pintype "passive"))
      (node (ref "Q2") (pin "4") (pinfunction "S_4") (pintype "bidirectional"))
      (node (ref "R15") (pin "2") (pinfunction "1_2") (pintype "passive"))
      (node (ref "U4") (pin "9") (pinfunction "SDA_9") (pintype "bidirectional"))
      (node (ref "X4") (pin "20") (pinfunction "MISO0/TX1/SDA0/PWM2A/GPIO20_20") (pintype "bidirectional"))
    )
    (net (code "101") (name "SDA_5V") (class "Default")
      (node (ref "Q2") (pin "3") (pinfunction "D_3") (pintype "bidirectional"))
      (node (ref "R15") (pin "3") (pinfunction "1_3") (pintype "passive"))
      (node (ref "X7") (pin "16") (pinfunction "DDAT_16") (pintype "bidirectional"))
    )
    (net (code "102") (name "SDCS{slash}SDIO_DAT3") (class "Default")
      (node (ref "R3") (pin "1") (pinfunction "1_1") (pintype "passive"))
      (node (ref "X1") (pin "2") (pinfunction "CS_2") (pintype "input"))
      (node (ref "X4") (pin "48") (pinfunction "GPIO39/MOSI0/RTS1/SCL1/PWM11B_48") (pintype "bidirectional"))
    )
    (net (code "103") (name "SDIO_DAT1") (class "Default")
      (node (ref "X1") (pin "8") (pinfunction "DAT1_8") (pintype "bidirectional"))
      (node (ref "X4") (pin "46") (pinfunction "GPIO37/CS0/RX1/SCL0/PWM10B_46") (pintype "bidirectional"))
    )
    (net (code "104") (name "SDIO_DAT2") (class "Default")
      (node (ref "X1") (pin "1") (pinfunction "DAT2_1") (pintype "bidirectional"))
      (node (ref "X4") (pin "47") (pinfunction "GPIO38/SCK0/CTS1/SDA1/PWM11A_47") (pintype "bidirectional"))
    )
    (net (code "105") (name "SD_DETECT") (class "Default")
      (node (ref "X1") (pin "CD1") (pinfunction "CARD_DETECT_CD1") (pintype "passive"))
      (node (ref "X1") (pin "CD2") (pinfunction "CARD_DETECT_CD2") (pintype "passive"))
      (node (ref "X4") (pin "42") (pinfunction "GPIO33/CS0/RX0/SCL0/PWM8B_42") (pintype "bidirectional"))
    )
    (net (code "106") (name "SPKN") (class "Default")
      (node (ref "U4") (pin "19") (pinfunction "SPKM_19") (pintype "output"))
      (node (ref "U4") (pin "23") (pinfunction "SPKM_23") (pintype "output"))
      (node (ref "X9") (pin "1") (pinfunction "1_1") (pintype "passive"))
    )
    (net (code "107") (name "SPKP") (class "Default")
      (node (ref "U4") (pin "22") (pinfunction "SPKP_22") (pintype "output"))
      (node (ref "U4") (pin "26") (pinfunction "SPKP_26") (pintype "output"))
      (node (ref "X9") (pin "2") (pinfunction "2_2") (pintype "passive"))
    )
    (net (code "108") (name "SWCLK") (class "Default")
      (node (ref "DEBUG") (pin "1") (pinfunction "1_1") (pintype "passive"))
      (node (ref "X4") (pin "33") (pinfunction "SWCLK_33") (pintype "bidirectional"))
    )
    (net (code "109") (name "SWDIO") (class "Default")
      (node (ref "DEBUG") (pin "3") (pinfunction "3_3") (pintype "passive"))
      (node (ref "X4") (pin "34") (pinfunction "SWDIO_34") (pintype "bidirectional"))
    )
    (net (code "110") (name "USBBOOT{slash}BUTTON1") (class "Default")
      (node (ref "BTN0") (pin "B") (pinfunction "S_B") (pintype "passive"))
      (node (ref "BTN0") (pin "B'") (pinfunction "S1_B'") (pintype "passive"))
      (node (ref "D3") (pin "C") (pinfunction "C_C") (pintype "passive"))
      (node (ref "JP3") (pin "12") (pinfunction "12_12") (pintype "passive"))
      (node (ref "TP1") (pin "P$1") (pinfunction "P$1_P$1") (pintype "bidirectional"))
      (node (ref "X4") (pin "77") (pinfunction "XPI_CS1/MISO0/TX0/SDA0/PWM0A/GPIO0_77") (pintype "bidirectional"))
    )
    (net (code "111") (name "USBH_D+") (class "Default")
      (node (ref "JP1") (pin "1") (pinfunction "1_1") (pintype "passive"))
      (node (ref "X4") (pin "78") (pinfunction "CS0/RX0/SCL0/PWM0B/GPIO1_78") (pintype "bidirectional"))
      (node (ref "X6") (pin "15") (pinfunction "D+U_15") (pintype "bidirectional"))
    )
    (net (code "112") (name "USBH_D-") (class "Default")
      (node (ref "JP1") (pin "2") (pinfunction "2_2") (pintype "passive"))
      (node (ref "X4") (pin "79") (pinfunction "SCK0/CTS0/SDA1/PWM1A/GPIO2_79") (pintype "bidirectional"))
      (node (ref "X6") (pin "14") (pinfunction "D-U_14") (pintype "bidirectional"))
    )
    (net (code "113") (name "USBH_PWR") (class "Default")
      (node (ref "Q1") (pin "1") (pinfunction "G_1") (pintype "bidirectional"))
      (node (ref "R8") (pin "2") (pinfunction "2_2") (pintype "passive"))
      (node (ref "X4") (pin "9") (pinfunction "MOSI1/RTS1/SCL1/PWM5B/GPIO11_9") (pintype "bidirectional"))
    )
    (net (code "114") (name "USB_D+") (class "Default")
      (node (ref "R25") (pin "1") (pinfunction "1_1") (pintype "passive"))
      (node (ref "X3") (pin "A6") (pinfunction "D+_A6") (pintype "bidirectional"))
      (node (ref "X3") (pin "B6") (pinfunction "D+_B6") (pintype "bidirectional"))
    )
    (net (code "115") (name "USB_D-") (class "Default")
      (node (ref "R24") (pin "1") (pinfunction "1_1") (pintype "passive"))
      (node (ref "X3") (pin "A7") (pinfunction "D-_A7") (pintype "bidirectional"))
      (node (ref "X3") (pin "B7") (pinfunction "D-_B7") (pintype "bidirectional"))
    )
    (net (code "116") (name "V33") (class "Default")
      (node (ref "C29") (pin "1") (pinfunction "1_1") (pintype "passive"))
      (node (ref "C30") (pin "1") (pinfunction "1_1") (pintype "passive"))
      (node (ref "X6") (pin "20") (pinfunction "V33_20") (pintype "power_in"))
    )
    (net (code "117") (name "VBUS") (class "Default")
      (node (ref "C31") (pin "1") (pinfunction "1_1") (pintype "passive"))
      (node (ref "C32") (pin "2") (pinfunction "2_2") (pintype "passive"))
      (node (ref "C46") (pin "2") (pinfunction "2_2") (pintype "passive"))
      (node (ref "C9") (pin "1") (pinfunction "1_1") (pintype "passive"))
      (node (ref "PTC1") (pin "1") (pinfunction "1_1") (pintype "passive"))
      (node (ref "X2") (pin "VBUS") (pinfunction "VBUS_VBUS") (pintype "power_in"))
      (node (ref "X5") (pin "VBUS") (pinfunction "VBUS_VBUS") (pintype "power_in"))
      (node (ref "X6") (pin "19") (pinfunction "V5_19") (pintype "power_in"))
    )
    (net (code "118") (name "VCC") (class "Default")
      (node (ref "SENSE1") (pin "2") (pinfunction "2_2") (pintype "passive"))
      (node (ref "SJ1") (pin "2") (pinfunction "2_2") (pintype "passive"))
    )
    (net (code "119") (name "VREG_AVDD") (class "Default")
      (node (ref "C4") (pin "1") (pinfunction "1_1") (pintype "passive"))
      (node (ref "R5") (pin "2") (pinfunction "2_2") (pintype "passive"))
      (node (ref "X4") (pin "61") (pinfunction "VREG_AVDD_61") (pintype "power_in"))
    )
    (net (code "120") (name "VUSB") (class "Default")
      (node (ref "Q3") (pin "2") (pinfunction "S_2") (pintype "passive"))
      (node (ref "R10") (pin "2") (pinfunction "2_2") (pintype "passive"))
      (node (ref "X3") (pin "A4B9") (pinfunction "VBUS_A4B9") (pintype "power_in"))
      (node (ref "X3") (pin "B4A9") (pinfunction "VBUS_B4A9") (pintype "power_in"))
    )
    (net (code "121") (name "XIN") (class "Default")
      (node (ref "C26") (pin "2") (pinfunction "2_2") (pintype "passive"))
      (node (ref "X4") (pin "30") (pinfunction "XIN_30") (pintype "input"))
      (node (ref "Y1") (pin "1") (pinfunction "1_1") (pintype "passive"))
    )
    (net (code "122") (name "XOUT") (class "Default")
      (node (ref "R23") (pin "2") (pinfunction "2_2") (pintype "passive"))
      (node (ref "X4") (pin "31") (pinfunction "XOUT_31") (pintype "output"))
    )
    (net (code "123") (name "unconnected-(LED5-DO-Pad3)") (class "Default")
      (node (ref "LED5") (pin "3") (pinfunction "DO_3") (pintype "output"))
    )
    (net (code "124") (name "unconnected-(SW2A-S-PadT2)") (class "Default")
      (node (ref "SW2") (pin "T2") (pinfunction "S_T2") (pintype "passive"))
    )
    (net (code "125") (name "unconnected-(U2-NC{slash}FB-Pad4)") (class "Default")
      (node (ref "U2") (pin "4") (pinfunction "NC/FB_4") (pintype "passive"))
    )
    (net (code "126") (name "unconnected-(U5-P4-Pad4)") (class "Default")
      (node (ref "U5") (pin "4") (pinfunction "P4_4") (pintype "bidirectional"))
    )
    (net (code "127") (name "unconnected-(U9-IO0{slash}ADC1_0-Pad12)") (class "Default")
      (node (ref "U9") (pin "12") (pinfunction "IO0/ADC1_0_12") (pintype "bidirectional"))
    )
    (net (code "128") (name "unconnected-(U9-IO1{slash}ADC1_1-Pad13)") (class "Default")
      (node (ref "U9") (pin "13") (pinfunction "IO1/ADC1_1_13") (pintype "bidirectional"))
    )
    (net (code "129") (name "unconnected-(U9-IO2{slash}ADC1_2-Pad5)") (class "Default")
      (node (ref "U9") (pin "5") (pinfunction "IO2/ADC1_2_5") (pintype "bidirectional"))
    )
    (net (code "130") (name "unconnected-(U9-IO4{slash}ADC1_4-Pad9)") (class "Default")
      (node (ref "U9") (pin "9") (pinfunction "IO4/ADC1_4_9") (pintype "bidirectional"))
    )
    (net (code "131") (name "unconnected-(U9-IO5{slash}ADC1_5-Pad10)") (class "Default")
      (node (ref "U9") (pin "10") (pinfunction "IO5/ADC1_5_10") (pintype "bidirectional"))
    )
    (net (code "132") (name "unconnected-(U9-IO12{slash}D--Pad17)") (class "Default")
      (node (ref "U9") (pin "17") (pinfunction "IO12/D-_17") (pintype "bidirectional"))
    )
    (net (code "133") (name "unconnected-(U9-IO13{slash}D+-Pad18)") (class "Default")
      (node (ref "U9") (pin "18") (pinfunction "IO13/D+_18") (pintype "bidirectional"))
    )
    (net (code "134") (name "unconnected-(U9-IO14-Pad19)") (class "Default")
      (node (ref "U9") (pin "19") (pinfunction "IO14_19") (pintype "bidirectional"))
    )
    (net (code "135") (name "unconnected-(U9-IO15-Pad20)") (class "Default")
      (node (ref "U9") (pin "20") (pinfunction "IO15_20") (pintype "bidirectional"))
    )
    (net (code "136") (name "unconnected-(U9-IO19-Pad25)") (class "Default")
      (node (ref "U9") (pin "25") (pinfunction "IO19_25") (pintype "bidirectional"))
    )
    (net (code "137") (name "unconnected-(U9-IO20-Pad26)") (class "Default")
      (node (ref "U9") (pin "26") (pinfunction "IO20_26") (pintype "bidirectional"))
    )
    (net (code "138") (name "unconnected-(U9-IO23-Pad29)") (class "Default")
      (node (ref "U9") (pin "29") (pinfunction "IO23_29") (pintype "bidirectional"))
    )
    (net (code "139") (name "unconnected-(X3A-SBU1-PadA8)") (class "Default")
      (node (ref "X3") (pin "A8") (pinfunction "SBU1_A8") (pintype "bidirectional"))
    )
    (net (code "140") (name "unconnected-(X3A-SBU2-PadB8)") (class "Default")
      (node (ref "X3") (pin "B8") (pinfunction "SBU2_B8") (pintype "bidirectional"))
    )
    (net (code "141") (name "unconnected-(X6-D+4-Pad6)") (class "Default")
      (node (ref "X6") (pin "6") (pinfunction "D+4_6") (pintype "bidirectional"))
    )
    (net (code "142") (name "unconnected-(X6-D-4-Pad5)") (class "Default")
      (node (ref "X6") (pin "5") (pinfunction "D-4_5") (pintype "bidirectional"))
    )
    (net (code "143") (name "unconnected-(X6-LED1-Pad22)") (class "Default")
      (node (ref "X6") (pin "22") (pinfunction "LED1_22") (pintype "bidirectional"))
    )
    (net (code "144") (name "unconnected-(X6-LED3{slash}SCL-Pad13)") (class "Default")
      (node (ref "X6") (pin "13") (pinfunction "LED3/SCL_13") (pintype "bidirectional"))
    )
    (net (code "145") (name "unconnected-(X6-PSELF-Pad18)") (class "Default")
      (node (ref "X6") (pin "18") (pinfunction "PSELF_18") (pintype "input"))
    )
    (net (code "146") (name "unconnected-(X6-~{OVCUR}-Pad1)") (class "Default")
      (node (ref "X6") (pin "1") (pinfunction "~{OVCUR}_1") (pintype "input"))
    )
    (net (code "147") (name "unconnected-(X6-~{PWREN}-Pad24)") (class "Default")
      (node (ref "X6") (pin "24") (pinfunction "~{PWREN}_24") (pintype "output"))
    )
    (net (code "148") (name "unconnected-(X6-~{RESET{slash}CDP}-Pad16)") (class "Default")
      (node (ref "X6") (pin "16") (pinfunction "~{RESET/CDP}_16") (pintype "input"))
    )
    (net (code "149") (name "unconnected-(X7A-CEC-Pad13)") (class "Default")
      (node (ref "X7") (pin "13") (pinfunction "CEC_13") (pintype "bidirectional"))
    )
    (net (code "150") (name "unconnected-(X7A-UTILITY-Pad14)") (class "Default")
      (node (ref "X7") (pin "14") (pinfunction "UTILITY_14") (pintype "bidirectional"))
    )
    (net (code "151") (name "~{RESET}") (class "Default")
      (node (ref "JP3") (pin "26") (pinfunction "26_26") (pintype "passive"))
      (node (ref "R21") (pin "2") (pinfunction "2_2") (pintype "passive"))
      (node (ref "SW1") (pin "B") (pinfunction "S_B") (pintype "passive"))
      (node (ref "SW1") (pin "B'") (pinfunction "S1_B'") (pintype "passive"))
      (node (ref "X4") (pin "35") (pinfunction "/RUN_35") (pintype "bidirectional"))
    )
  )
)
